# actuator_control_board_1_0_0.net
KiCad netlist of a schematic drawn in EAGLE
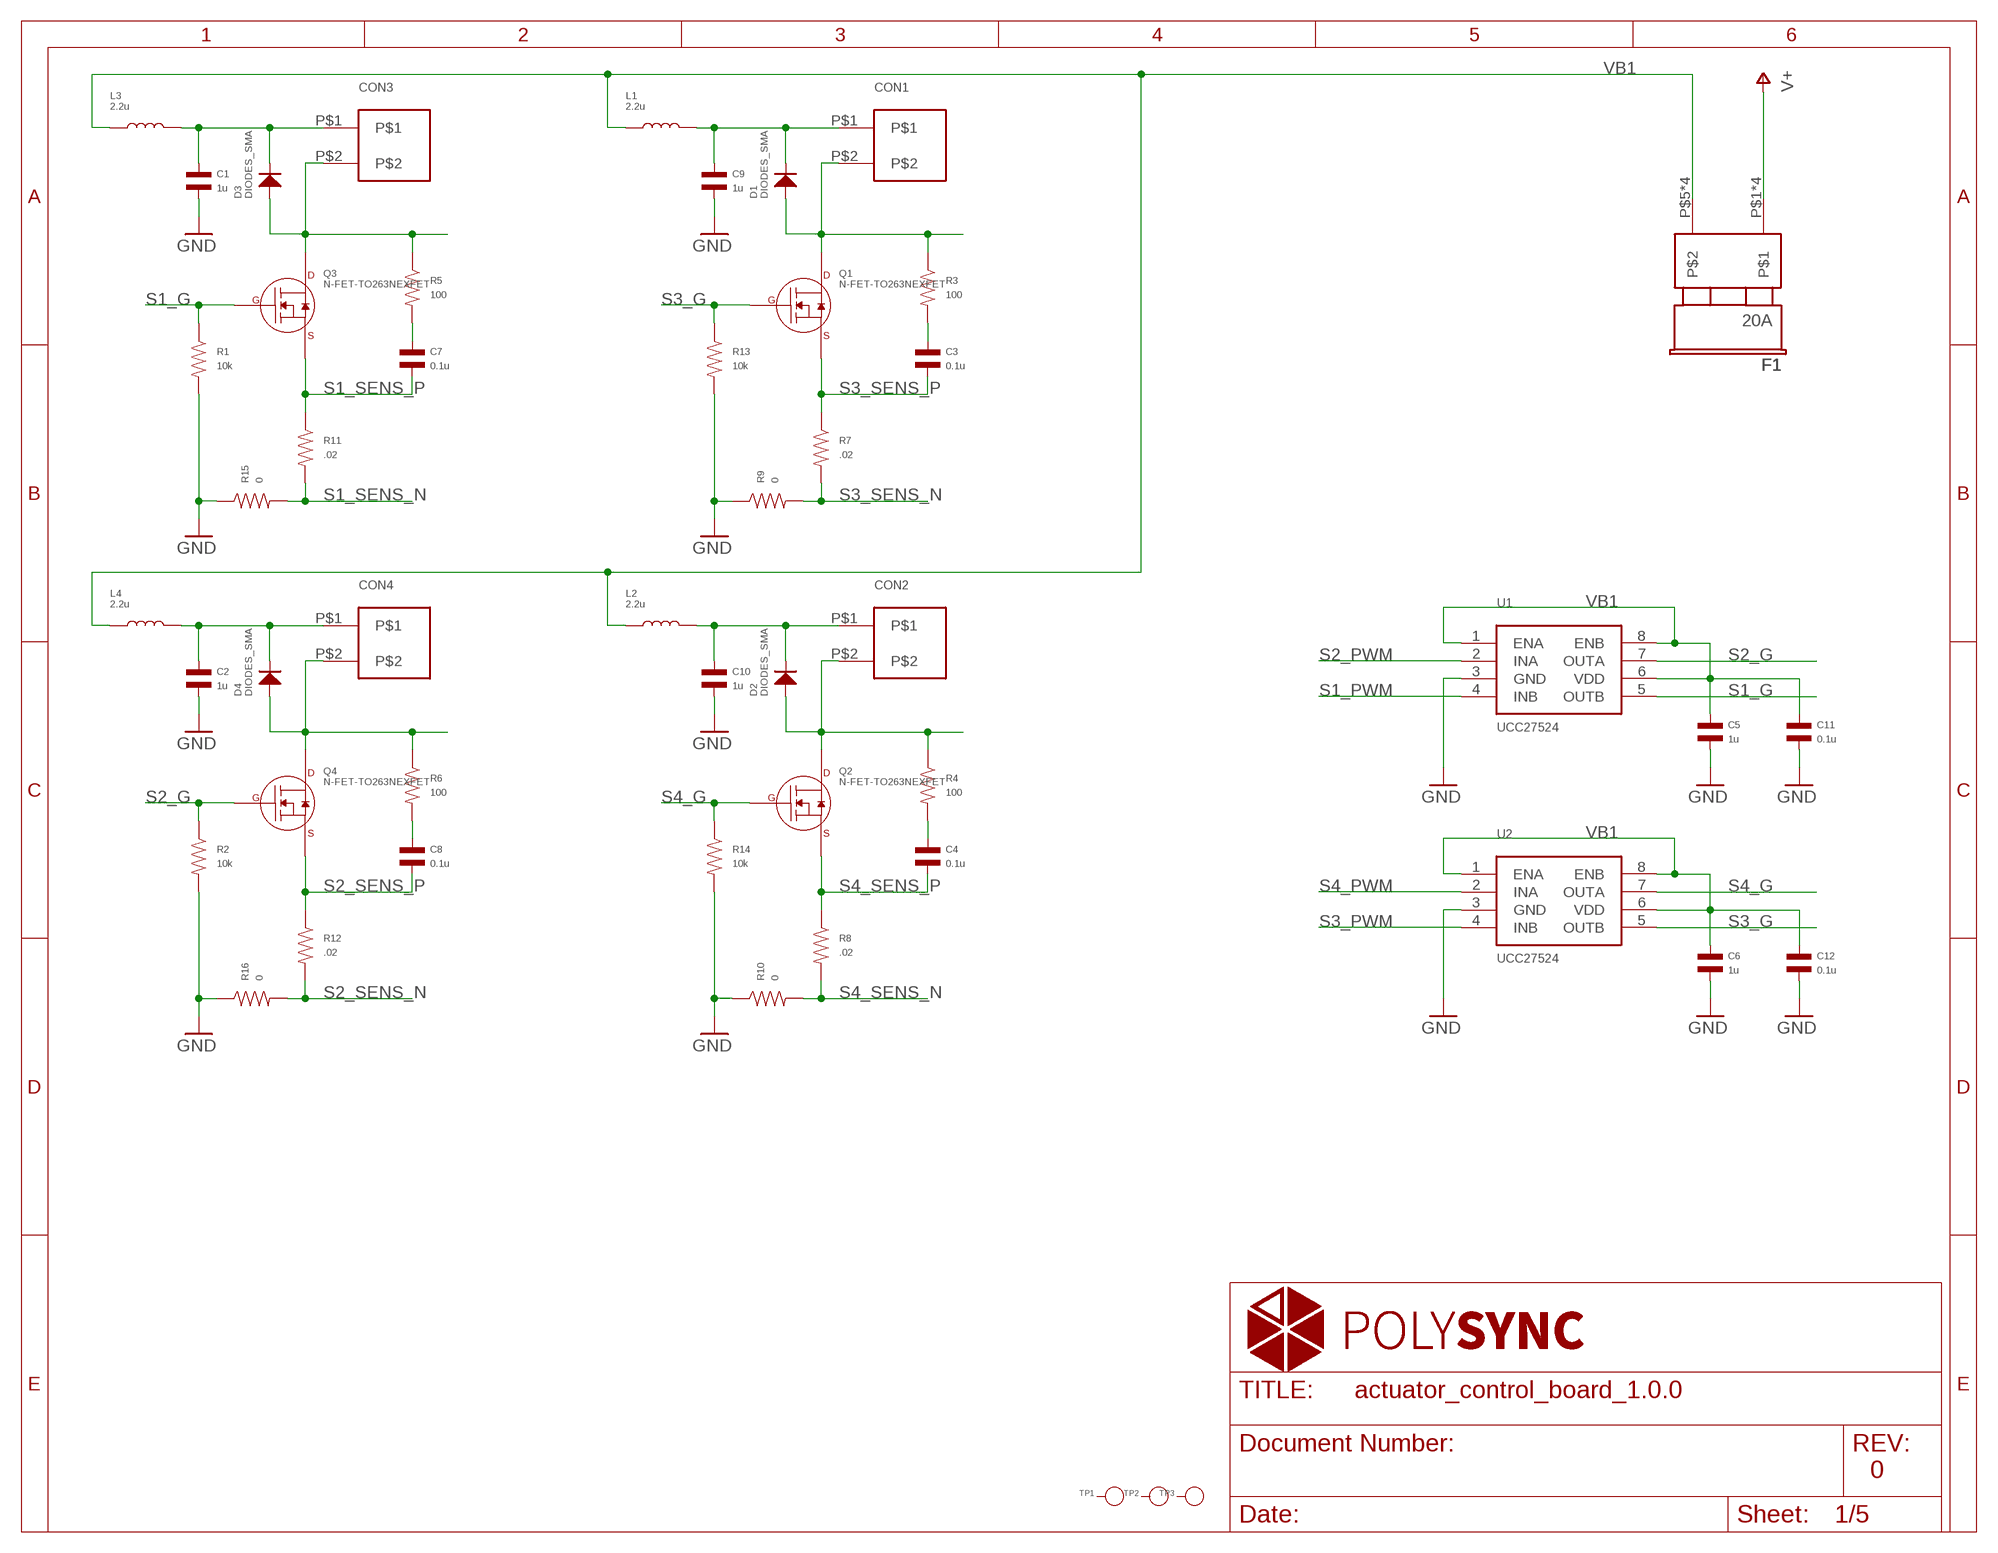
[diagram p0: schematic, sheet 1]
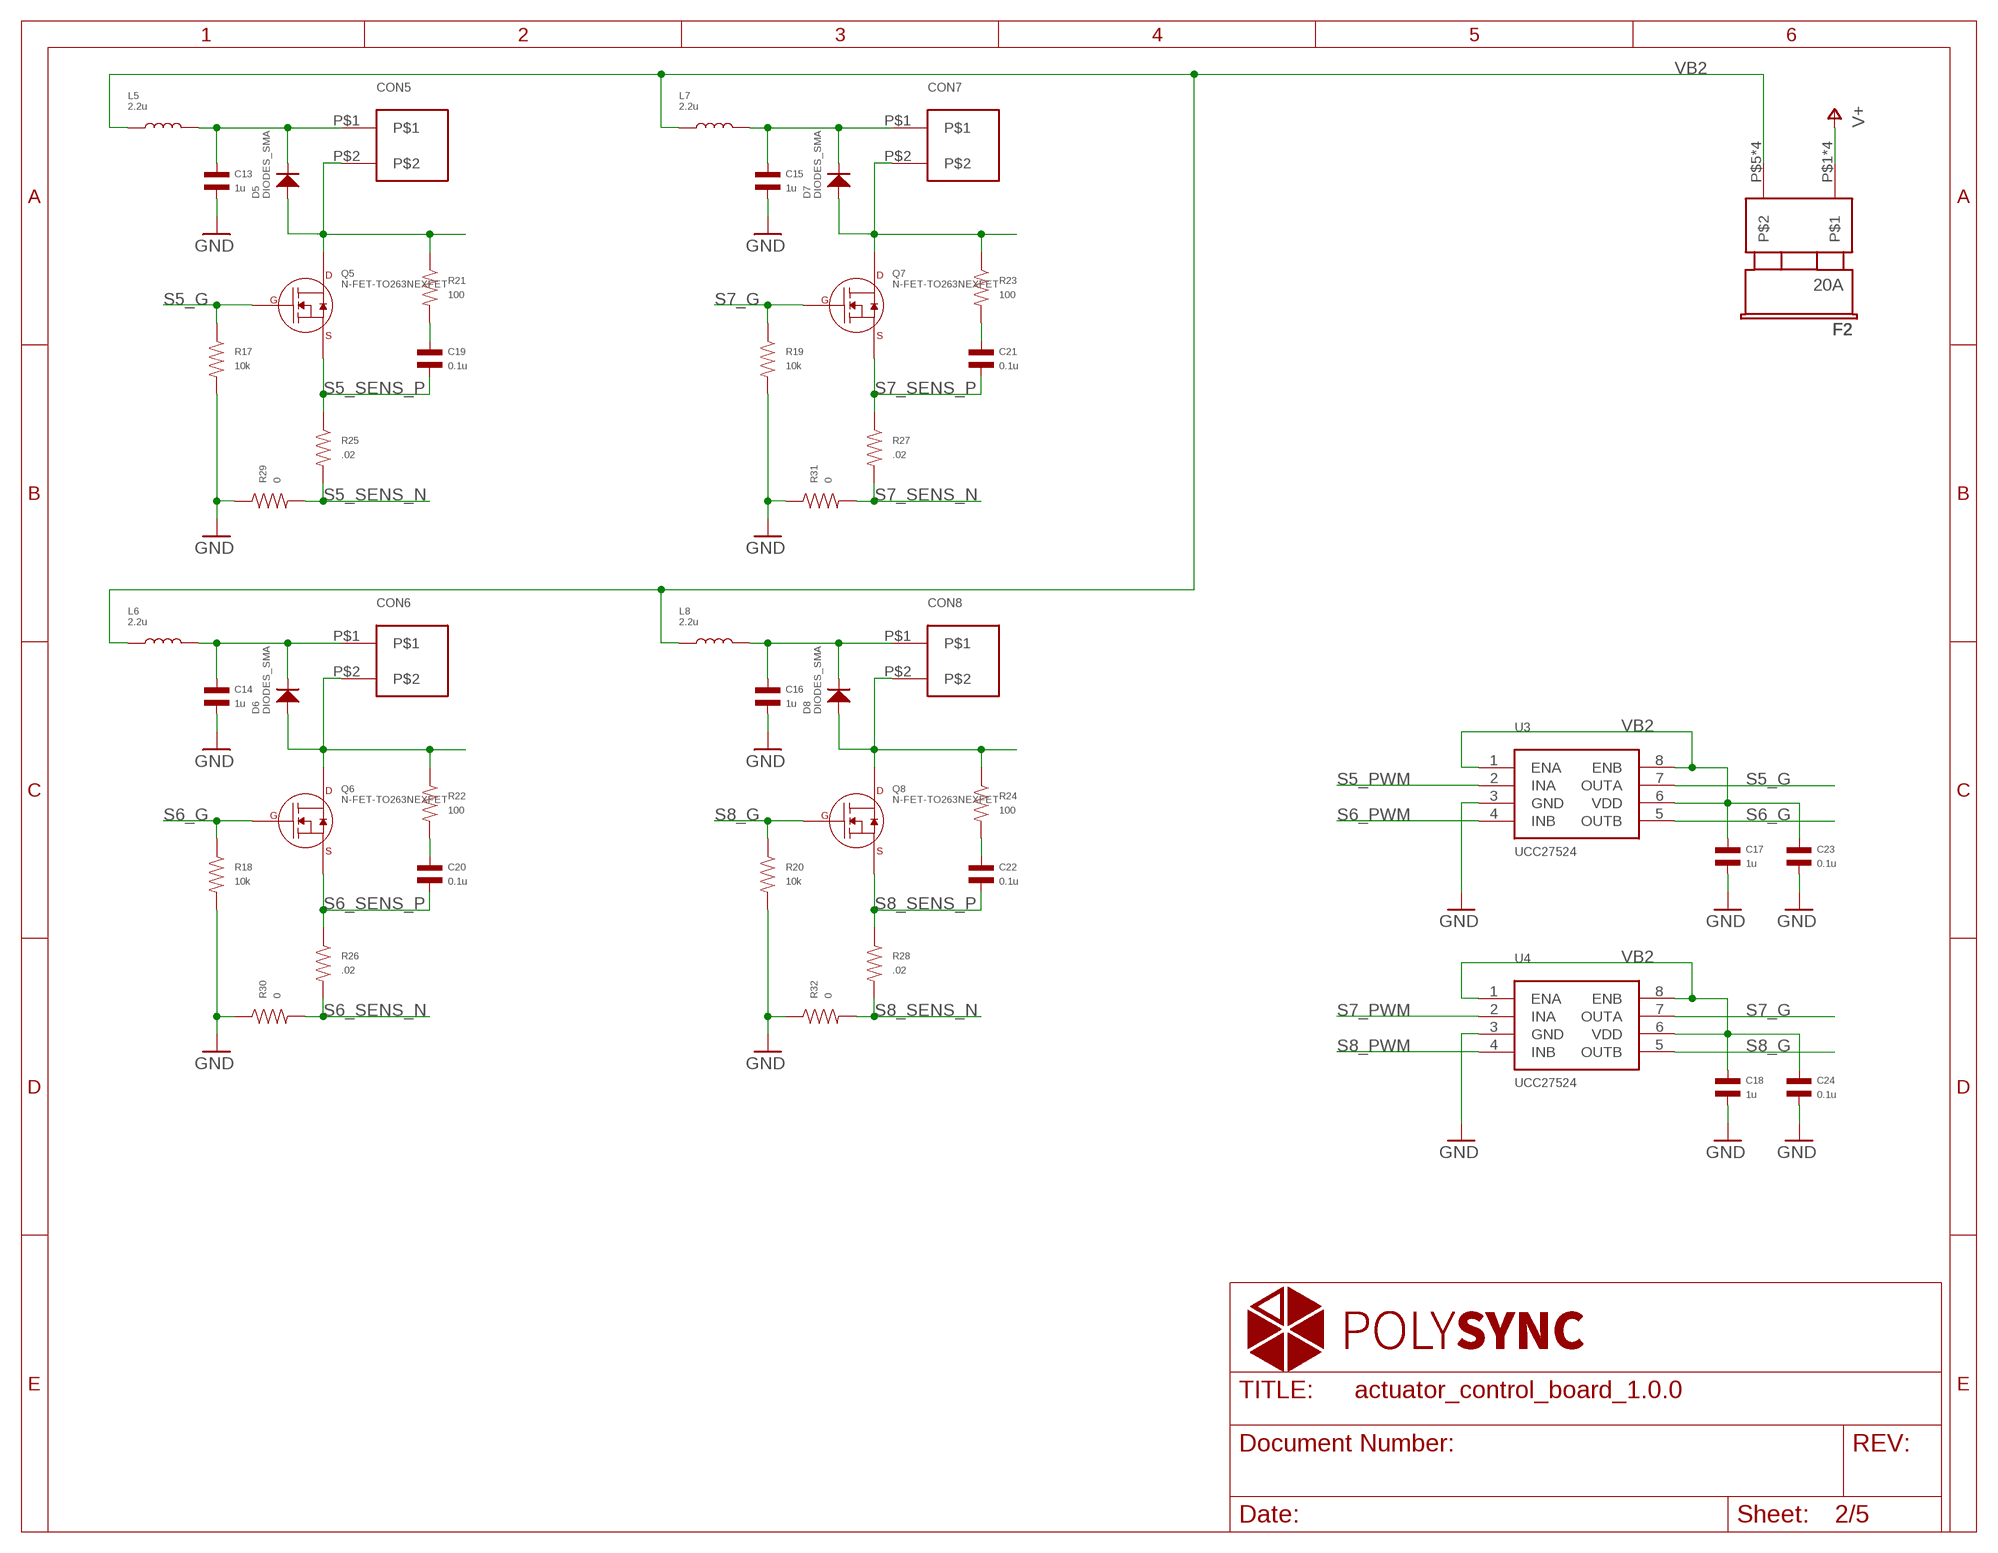
[diagram p1: schematic, sheet 2]
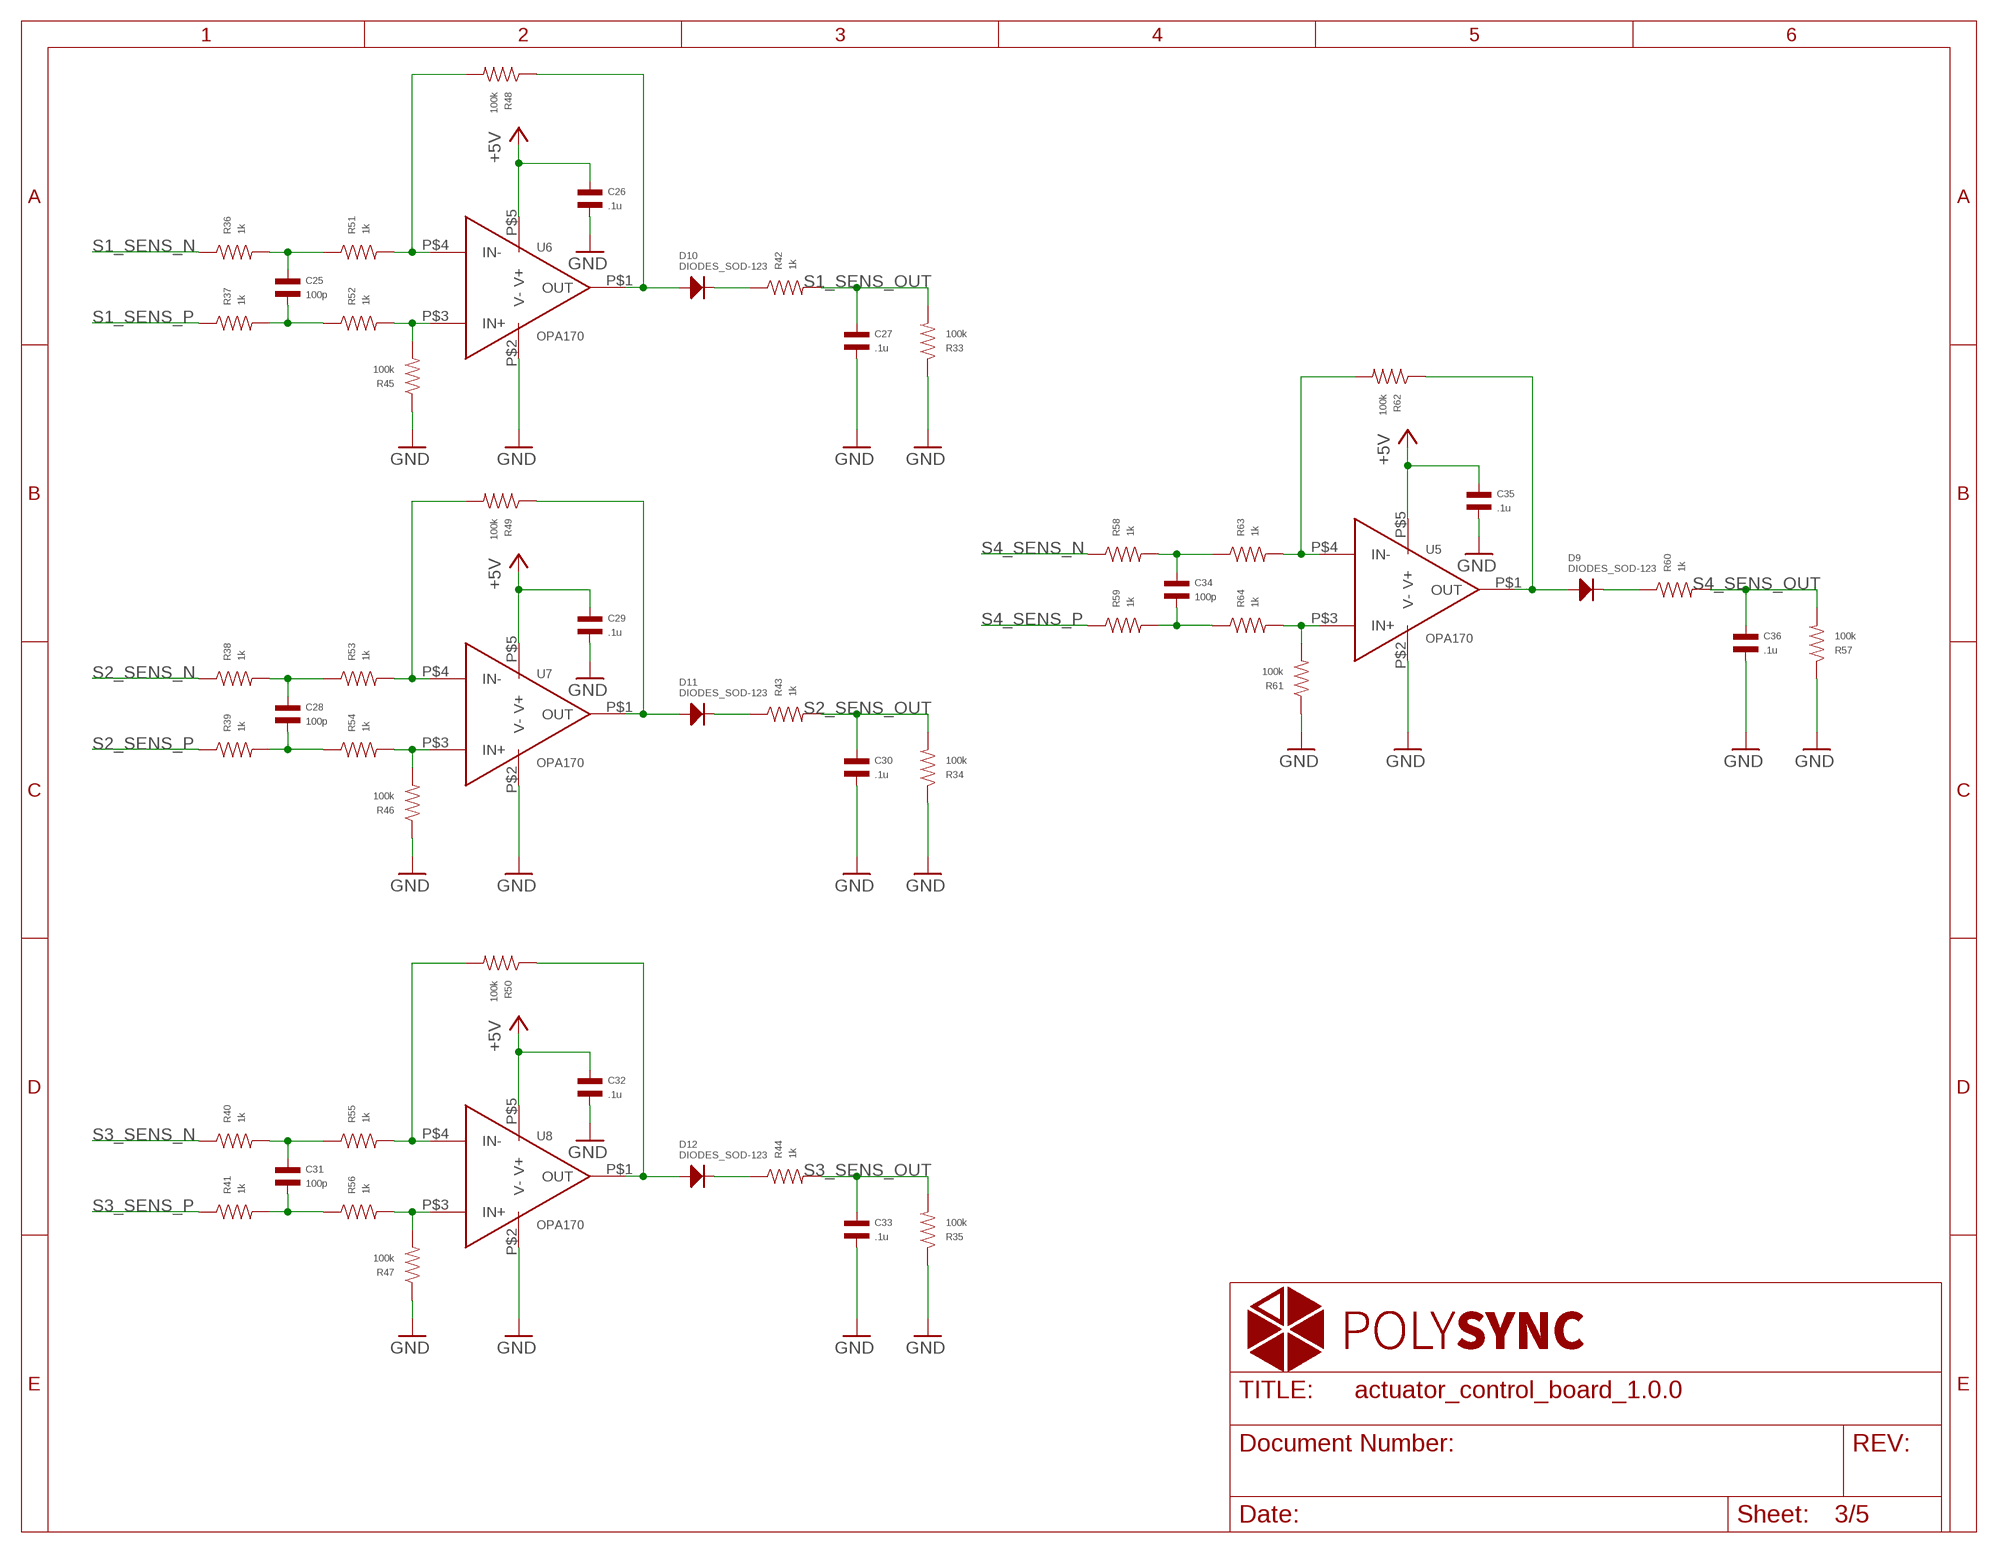
[diagram p2: schematic, sheet 3]
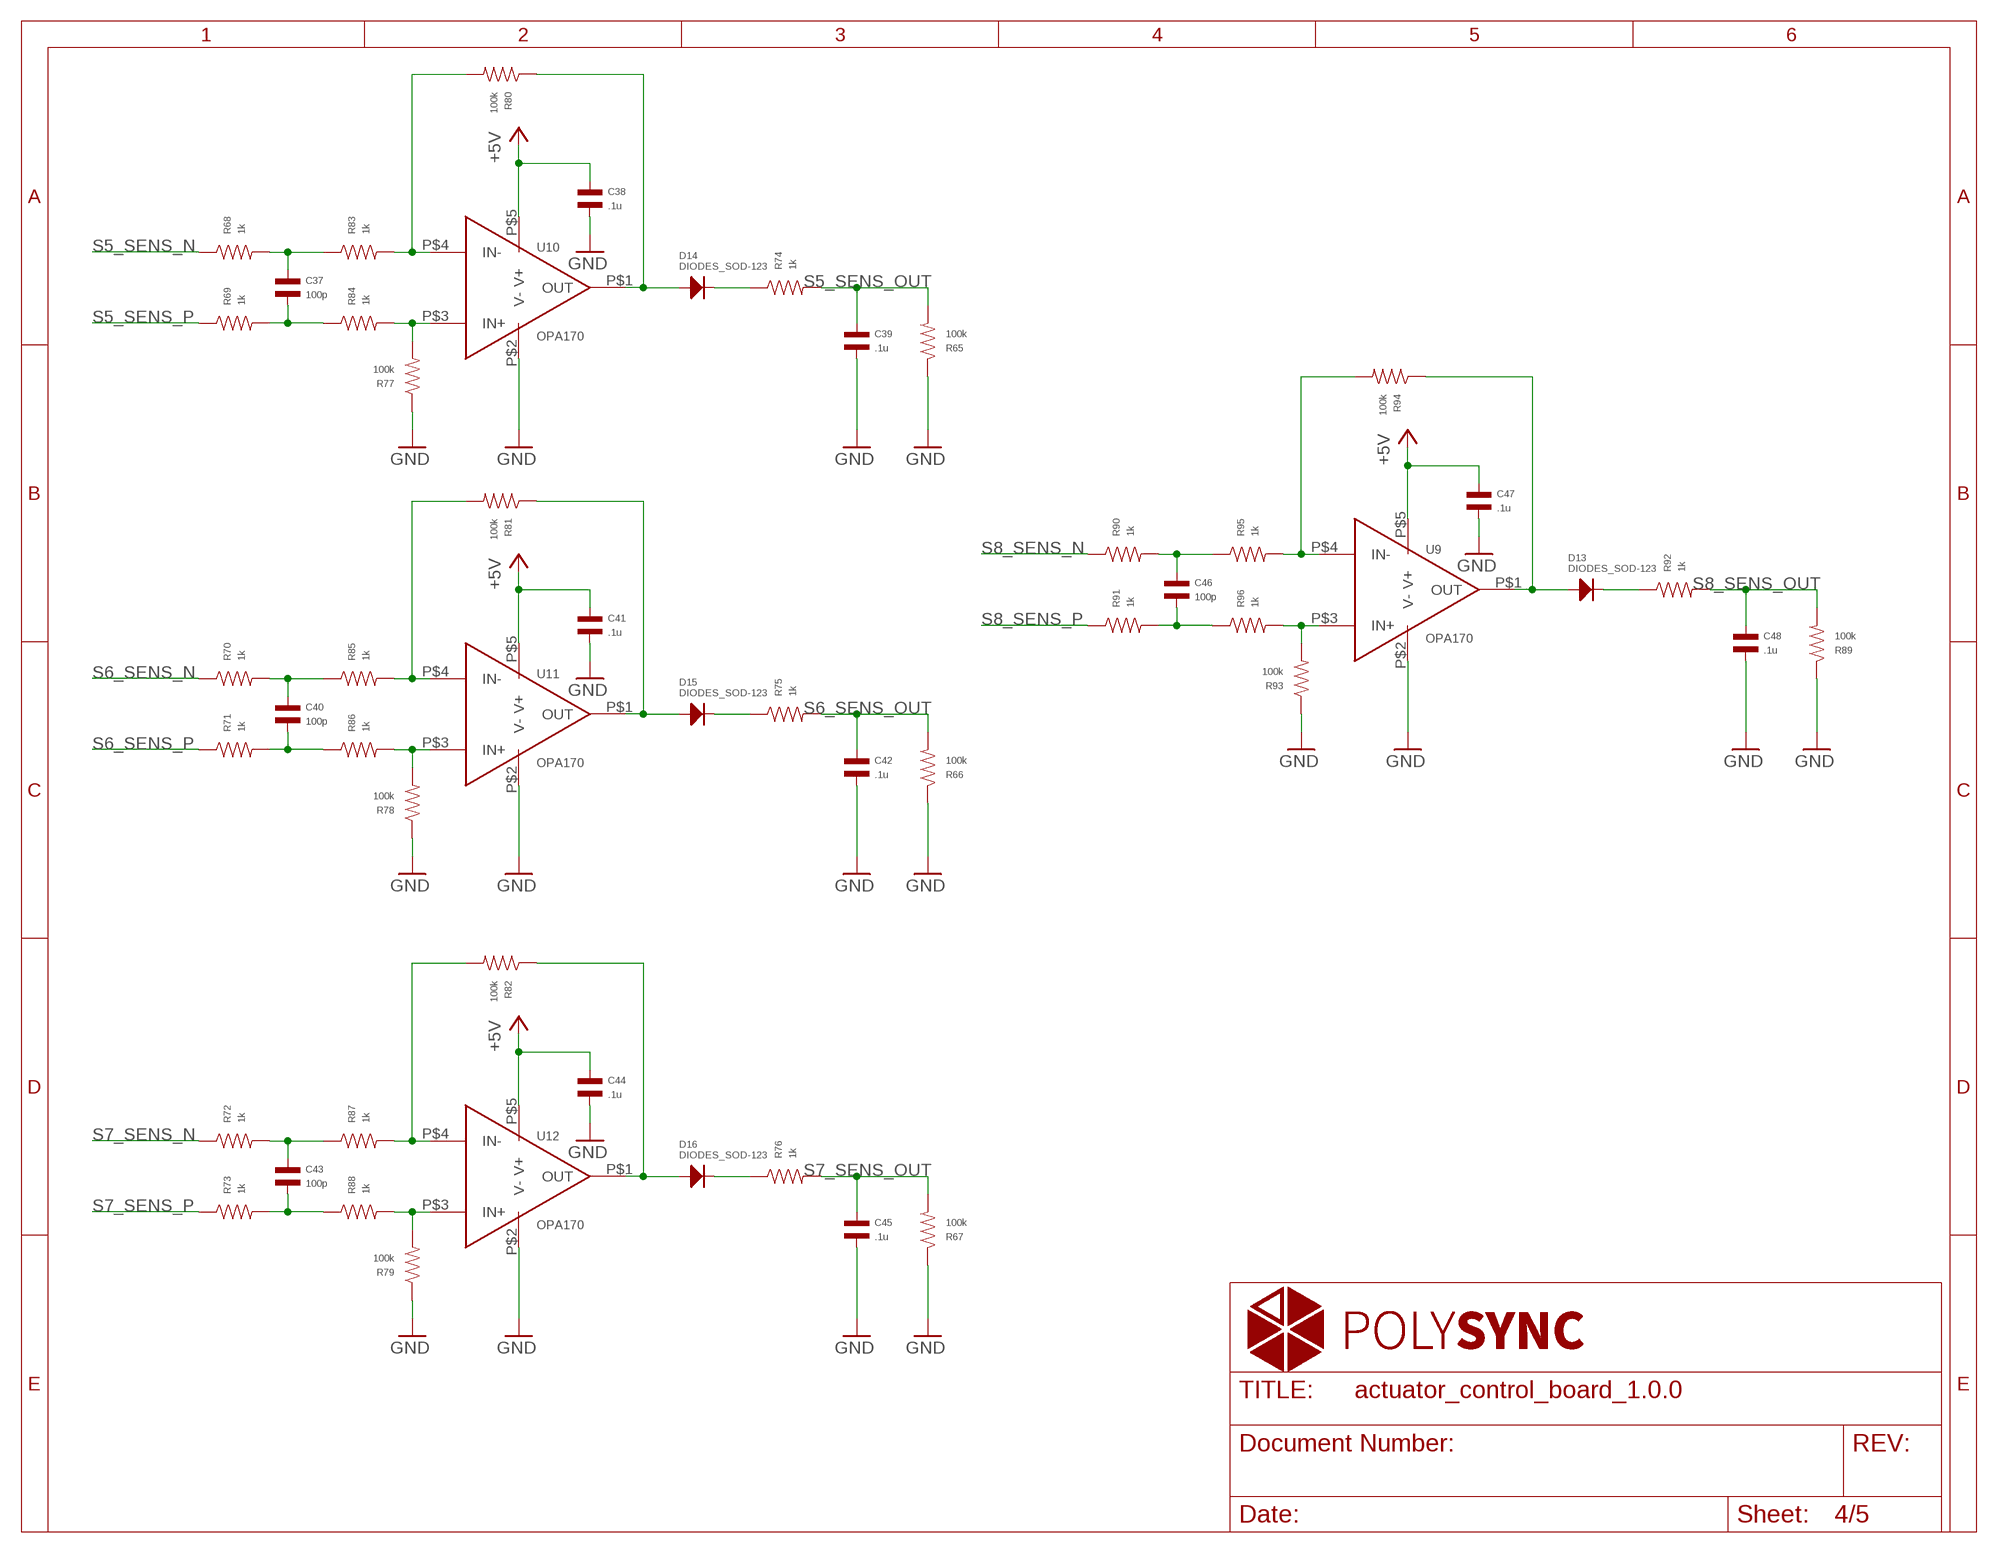
[diagram p3: schematic, sheet 4]
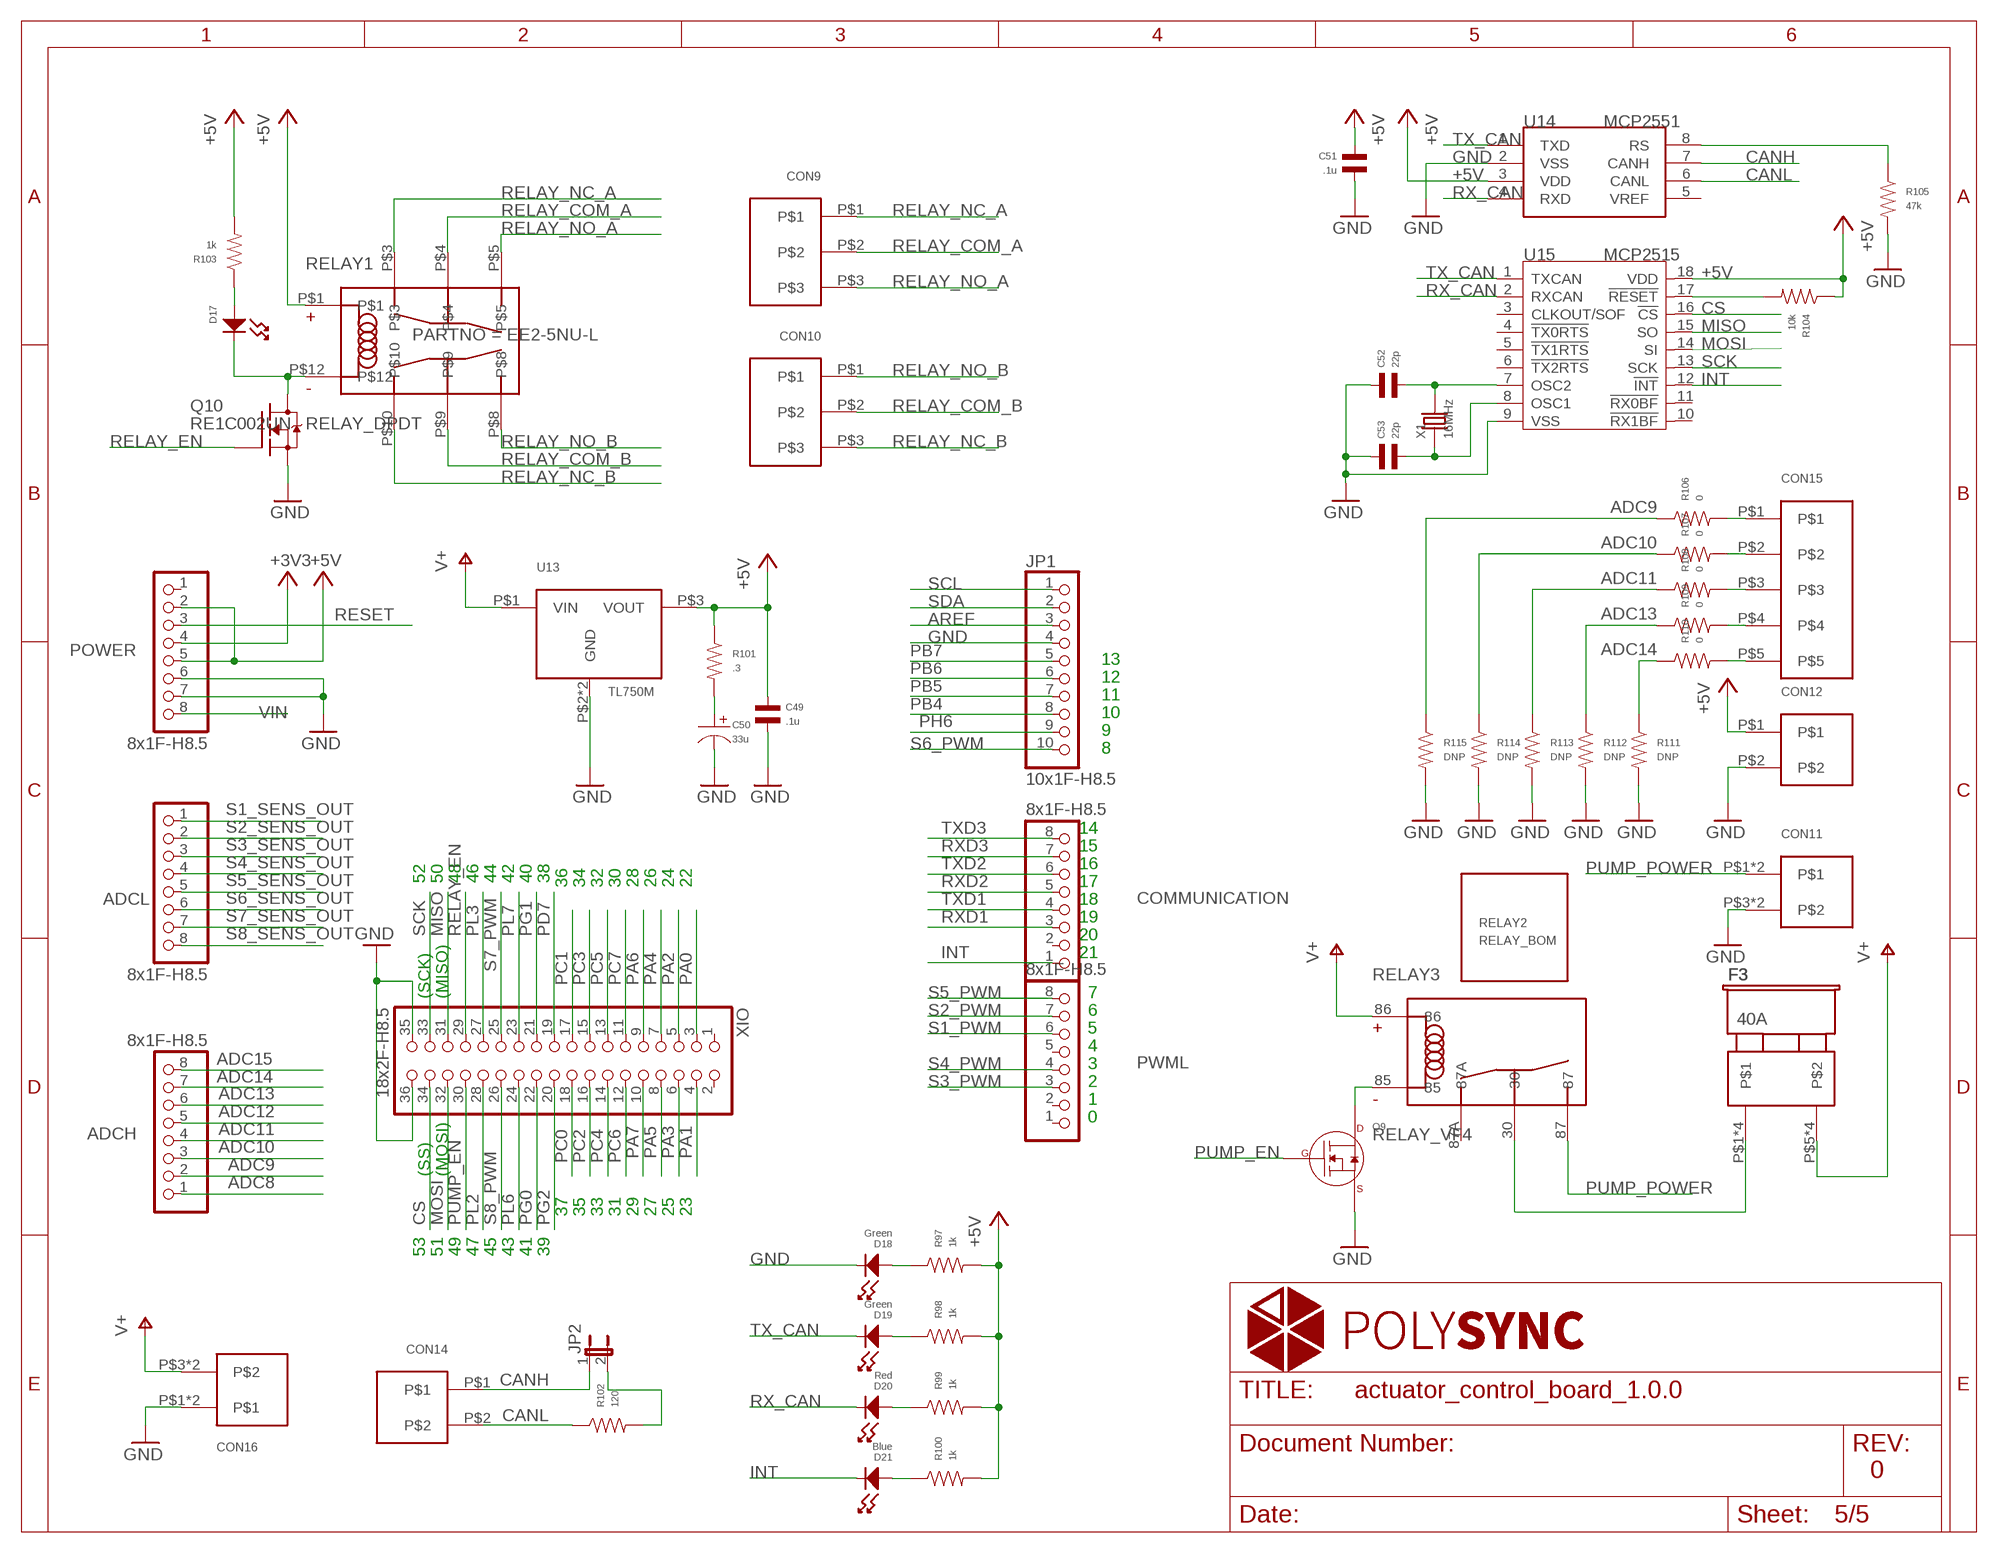
[diagram p4: schematic, sheet 5]

(export (version "E")
  (design (tool "Eeschema 10.0.6"))
  (components
    (comp (ref "C37")
      (value "100p")
      (footprint "eagle-import:C0402")
      (libsource (lib "eagle-import") (part "CAPACITOR_NP_0402"))
    )
    (comp (ref "C38")
      (value ".1u")
      (footprint "eagle-import:C0402")
      (libsource (lib "eagle-import") (part "CAPACITOR_NP_0402"))
    )
    (comp (ref "C39")
      (value ".1u")
      (footprint "eagle-import:C0402")
      (libsource (lib "eagle-import") (part "CAPACITOR_NP_0402"))
    )
    (comp (ref "C40")
      (value "100p")
      (footprint "eagle-import:C0402")
      (libsource (lib "eagle-import") (part "CAPACITOR_NP_0402"))
    )
    (comp (ref "C41")
      (value ".1u")
      (footprint "eagle-import:C0402")
      (libsource (lib "eagle-import") (part "CAPACITOR_NP_0402"))
    )
    (comp (ref "C42")
      (value ".1u")
      (footprint "eagle-import:C0402")
      (libsource (lib "eagle-import") (part "CAPACITOR_NP_0402"))
    )
    (comp (ref "C43")
      (value "100p")
      (footprint "eagle-import:C0402")
      (libsource (lib "eagle-import") (part "CAPACITOR_NP_0402"))
    )
    (comp (ref "C44")
      (value ".1u")
      (footprint "eagle-import:C0402")
      (libsource (lib "eagle-import") (part "CAPACITOR_NP_0402"))
    )
    (comp (ref "C45")
      (value ".1u")
      (footprint "eagle-import:C0402")
      (libsource (lib "eagle-import") (part "CAPACITOR_NP_0402"))
    )
    (comp (ref "C46")
      (value "100p")
      (footprint "eagle-import:C0402")
      (libsource (lib "eagle-import") (part "CAPACITOR_NP_0402"))
    )
    (comp (ref "C47")
      (value ".1u")
      (footprint "eagle-import:C0402")
      (libsource (lib "eagle-import") (part "CAPACITOR_NP_0402"))
    )
    (comp (ref "C48")
      (value ".1u")
      (footprint "eagle-import:C0402")
      (libsource (lib "eagle-import") (part "CAPACITOR_NP_0402"))
    )
    (comp (ref "D13")
      (value "DIODES_SOD-123")
      (footprint "eagle-import:SOD-123")
      (fields (field (name "HOUSEPART") "NO"))
      (libsource (lib "eagle-import") (part "DIODES_SOD-123"))
    )
    (comp (ref "D14")
      (value "DIODES_SOD-123")
      (footprint "eagle-import:SOD-123")
      (fields (field (name "HOUSEPART") "NO"))
      (libsource (lib "eagle-import") (part "DIODES_SOD-123"))
    )
    (comp (ref "D15")
      (value "DIODES_SOD-123")
      (footprint "eagle-import:SOD-123")
      (fields (field (name "HOUSEPART") "NO"))
      (libsource (lib "eagle-import") (part "DIODES_SOD-123"))
    )
    (comp (ref "D16")
      (value "DIODES_SOD-123")
      (footprint "eagle-import:SOD-123")
      (fields (field (name "HOUSEPART") "NO"))
      (libsource (lib "eagle-import") (part "DIODES_SOD-123"))
    )
    (comp (ref "R65")
      (value "100k")
      (footprint "eagle-import:R0402")
      (libsource (lib "eagle-import") (part "RESISTOR_0402"))
    )
    (comp (ref "R66")
      (value "100k")
      (footprint "eagle-import:R0402")
      (libsource (lib "eagle-import") (part "RESISTOR_0402"))
    )
    (comp (ref "R67")
      (value "100k")
      (footprint "eagle-import:R0402")
      (libsource (lib "eagle-import") (part "RESISTOR_0402"))
    )
    (comp (ref "R68")
      (value "1k")
      (footprint "eagle-import:R0402")
      (libsource (lib "eagle-import") (part "RESISTOR_0402"))
    )
    (comp (ref "R69")
      (value "1k")
      (footprint "eagle-import:R0402")
      (libsource (lib "eagle-import") (part "RESISTOR_0402"))
    )
    (comp (ref "R70")
      (value "1k")
      (footprint "eagle-import:R0402")
      (libsource (lib "eagle-import") (part "RESISTOR_0402"))
    )
    (comp (ref "R71")
      (value "1k")
      (footprint "eagle-import:R0402")
      (libsource (lib "eagle-import") (part "RESISTOR_0402"))
    )
    (comp (ref "R72")
      (value "1k")
      (footprint "eagle-import:R0402")
      (libsource (lib "eagle-import") (part "RESISTOR_0402"))
    )
    (comp (ref "R73")
      (value "1k")
      (footprint "eagle-import:R0402")
      (libsource (lib "eagle-import") (part "RESISTOR_0402"))
    )
    (comp (ref "R74")
      (value "1k")
      (footprint "eagle-import:R0402")
      (libsource (lib "eagle-import") (part "RESISTOR_0402"))
    )
    (comp (ref "R75")
      (value "1k")
      (footprint "eagle-import:R0402")
      (libsource (lib "eagle-import") (part "RESISTOR_0402"))
    )
    (comp (ref "R76")
      (value "1k")
      (footprint "eagle-import:R0402")
      (libsource (lib "eagle-import") (part "RESISTOR_0402"))
    )
    (comp (ref "R77")
      (value "100k")
      (footprint "eagle-import:R0402")
      (libsource (lib "eagle-import") (part "RESISTOR_0402"))
    )
    (comp (ref "R78")
      (value "100k")
      (footprint "eagle-import:R0402")
      (libsource (lib "eagle-import") (part "RESISTOR_0402"))
    )
    (comp (ref "R79")
      (value "100k")
      (footprint "eagle-import:R0402")
      (libsource (lib "eagle-import") (part "RESISTOR_0402"))
    )
    (comp (ref "R80")
      (value "100k")
      (footprint "eagle-import:R0402")
      (libsource (lib "eagle-import") (part "RESISTOR_0402"))
    )
    (comp (ref "R81")
      (value "100k")
      (footprint "eagle-import:R0402")
      (libsource (lib "eagle-import") (part "RESISTOR_0402"))
    )
    (comp (ref "R82")
      (value "100k")
      (footprint "eagle-import:R0402")
      (libsource (lib "eagle-import") (part "RESISTOR_0402"))
    )
    (comp (ref "R83")
      (value "1k")
      (footprint "eagle-import:R0402")
      (libsource (lib "eagle-import") (part "RESISTOR_0402"))
    )
    (comp (ref "R84")
      (value "1k")
      (footprint "eagle-import:R0402")
      (libsource (lib "eagle-import") (part "RESISTOR_0402"))
    )
    (comp (ref "R85")
      (value "1k")
      (footprint "eagle-import:R0402")
      (libsource (lib "eagle-import") (part "RESISTOR_0402"))
    )
    (comp (ref "R86")
      (value "1k")
      (footprint "eagle-import:R0402")
      (libsource (lib "eagle-import") (part "RESISTOR_0402"))
    )
    (comp (ref "R87")
      (value "1k")
      (footprint "eagle-import:R0402")
      (libsource (lib "eagle-import") (part "RESISTOR_0402"))
    )
    (comp (ref "R88")
      (value "1k")
      (footprint "eagle-import:R0402")
      (libsource (lib "eagle-import") (part "RESISTOR_0402"))
    )
    (comp (ref "R89")
      (value "100k")
      (footprint "eagle-import:R0402")
      (libsource (lib "eagle-import") (part "RESISTOR_0402"))
    )
    (comp (ref "R90")
      (value "1k")
      (footprint "eagle-import:R0402")
      (libsource (lib "eagle-import") (part "RESISTOR_0402"))
    )
    (comp (ref "R91")
      (value "1k")
      (footprint "eagle-import:R0402")
      (libsource (lib "eagle-import") (part "RESISTOR_0402"))
    )
    (comp (ref "R92")
      (value "1k")
      (footprint "eagle-import:R0402")
      (libsource (lib "eagle-import") (part "RESISTOR_0402"))
    )
    (comp (ref "R93")
      (value "100k")
      (footprint "eagle-import:R0402")
      (libsource (lib "eagle-import") (part "RESISTOR_0402"))
    )
    (comp (ref "R94")
      (value "100k")
      (footprint "eagle-import:R0402")
      (libsource (lib "eagle-import") (part "RESISTOR_0402"))
    )
    (comp (ref "R95")
      (value "1k")
      (footprint "eagle-import:R0402")
      (libsource (lib "eagle-import") (part "RESISTOR_0402"))
    )
    (comp (ref "R96")
      (value "1k")
      (footprint "eagle-import:R0402")
      (libsource (lib "eagle-import") (part "RESISTOR_0402"))
    )
    (comp (ref "U9")
      (value "OPA170")
      (footprint "eagle-import:SOT-23-5")
      (libsource (lib "eagle-import") (part "OPA170"))
    )
    (comp (ref "U10")
      (value "OPA170")
      (footprint "eagle-import:SOT-23-5")
      (libsource (lib "eagle-import") (part "OPA170"))
    )
    (comp (ref "U11")
      (value "OPA170")
      (footprint "eagle-import:SOT-23-5")
      (libsource (lib "eagle-import") (part "OPA170"))
    )
    (comp (ref "U12")
      (value "OPA170")
      (footprint "eagle-import:SOT-23-5")
      (libsource (lib "eagle-import") (part "OPA170"))
    )
    (comp (ref "C1")
      (value "1u")
      (footprint "eagle-import:C1206")
      (libsource (lib "eagle-import") (part "CAPACITOR_NP_1206"))
    )
    (comp (ref "C2")
      (value "1u")
      (footprint "eagle-import:C1206")
      (libsource (lib "eagle-import") (part "CAPACITOR_NP_1206"))
    )
    (comp (ref "C3")
      (value "0.1u")
      (footprint "eagle-import:C0805")
      (libsource (lib "eagle-import") (part "CAPACITOR_NP_0805"))
    )
    (comp (ref "C4")
      (value "0.1u")
      (footprint "eagle-import:C0805")
      (libsource (lib "eagle-import") (part "CAPACITOR_NP_0805"))
    )
    (comp (ref "C5")
      (value "1u")
      (footprint "eagle-import:C1206")
      (libsource (lib "eagle-import") (part "CAPACITOR_NP_1206"))
    )
    (comp (ref "C6")
      (value "1u")
      (footprint "eagle-import:C1206")
      (libsource (lib "eagle-import") (part "CAPACITOR_NP_1206"))
    )
    (comp (ref "C7")
      (value "0.1u")
      (footprint "eagle-import:C0805")
      (libsource (lib "eagle-import") (part "CAPACITOR_NP_0805"))
    )
    (comp (ref "C8")
      (value "0.1u")
      (footprint "eagle-import:C0805")
      (libsource (lib "eagle-import") (part "CAPACITOR_NP_0805"))
    )
    (comp (ref "C9")
      (value "1u")
      (footprint "eagle-import:C1206")
      (libsource (lib "eagle-import") (part "CAPACITOR_NP_1206"))
    )
    (comp (ref "C10")
      (value "1u")
      (footprint "eagle-import:C1206")
      (libsource (lib "eagle-import") (part "CAPACITOR_NP_1206"))
    )
    (comp (ref "C11")
      (value "0.1u")
      (footprint "eagle-import:C0805")
      (libsource (lib "eagle-import") (part "CAPACITOR_NP_0805"))
    )
    (comp (ref "C12")
      (value "0.1u")
      (footprint "eagle-import:C0805")
      (libsource (lib "eagle-import") (part "CAPACITOR_NP_0805"))
    )
    (comp (ref "CON1")
      (value "CON23.5MM")
      (footprint "eagle-import:PHOENIX_2_45")
      (libsource (lib "eagle-import") (part "CON23.5MM"))
    )
    (comp (ref "CON2")
      (value "CON23.5MM")
      (footprint "eagle-import:PHOENIX_2_45")
      (libsource (lib "eagle-import") (part "CON23.5MM"))
    )
    (comp (ref "CON3")
      (value "CON23.5MM")
      (footprint "eagle-import:PHOENIX_2_45")
      (libsource (lib "eagle-import") (part "CON23.5MM"))
    )
    (comp (ref "CON4")
      (value "CON23.5MM")
      (footprint "eagle-import:PHOENIX_2_45")
      (libsource (lib "eagle-import") (part "CON23.5MM"))
    )
    (comp (ref "D1")
      (value "DIODES_SMA")
      (footprint "eagle-import:SMA")
      (fields (field (name "HOUSEPART") "NO"))
      (libsource (lib "eagle-import") (part "DIODES_SMA"))
    )
    (comp (ref "D2")
      (value "DIODES_SMA")
      (footprint "eagle-import:SMA")
      (fields (field (name "HOUSEPART") "NO"))
      (libsource (lib "eagle-import") (part "DIODES_SMA"))
    )
    (comp (ref "D3")
      (value "DIODES_SMA")
      (footprint "eagle-import:SMA")
      (fields
        (field (name "HOUSEPART") "NO")
        (field (name "MFG") "Diodes Inc")
        (field (name "MPN") "US1B-13-F")
      )
      (libsource (lib "eagle-import") (part "DIODES_SMA"))
    )
    (comp (ref "D4")
      (value "DIODES_SMA")
      (footprint "eagle-import:SMA")
      (fields (field (name "HOUSEPART") "NO"))
      (libsource (lib "eagle-import") (part "DIODES_SMA"))
    )
    (comp (ref "F1")
      (value "20A")
      (footprint "eagle-import:FUSE_ATO")
      (fields (field (name "MFG") "Littelfuse") (field (name "PARTNO") "178.6165.0001"))
      (libsource (lib "eagle-import") (part "FUSE"))
    )
    (comp (ref "L1")
      (value "2.2u")
      (footprint "eagle-import:SRP7050")
      (fields (field (name "MFG") "Bourns") (field (name "PARTNO") "SRP7050TA-2R2M"))
      (libsource (lib "eagle-import") (part "INDUCTORSRP7050"))
    )
    (comp (ref "L2")
      (value "2.2u")
      (footprint "eagle-import:SRP7050")
      (fields (field (name "MFG") "Bourns") (field (name "PARTNO") "SRP7050TA-2R2M"))
      (libsource (lib "eagle-import") (part "INDUCTORSRP7050"))
    )
    (comp (ref "L3")
      (value "2.2u")
      (footprint "eagle-import:SRP7050")
      (fields (field (name "MFG") "Bourns") (field (name "PARTNO") "SRP7050TA-2R2M"))
      (libsource (lib "eagle-import") (part "INDUCTORSRP7050"))
    )
    (comp (ref "L4")
      (value "2.2u")
      (footprint "eagle-import:SRP7050")
      (fields (field (name "MFG") "Bourns") (field (name "PARTNO") "SRP7050TA-2R2M"))
      (libsource (lib "eagle-import") (part "INDUCTORSRP7050"))
    )
    (comp (ref "Q1")
      (value "N-FET-TO263NEXFET")
      (footprint "eagle-import:SON8-DQJ")
      (libsource (lib "eagle-import") (part "N-FET-TO263NEXFET"))
    )
    (comp (ref "Q2")
      (value "N-FET-TO263NEXFET")
      (footprint "eagle-import:SON8-DQJ")
      (libsource (lib "eagle-import") (part "N-FET-TO263NEXFET"))
    )
    (comp (ref "Q3")
      (value "N-FET-TO263NEXFET")
      (footprint "eagle-import:SON8-DQJ")
      (libsource (lib "eagle-import") (part "N-FET-TO263NEXFET"))
    )
    (comp (ref "Q4")
      (value "N-FET-TO263NEXFET")
      (footprint "eagle-import:SON8-DQJ")
      (libsource (lib "eagle-import") (part "N-FET-TO263NEXFET"))
    )
    (comp (ref "R1")
      (value "10k")
      (footprint "eagle-import:R0402")
      (libsource (lib "eagle-import") (part "RESISTOR_0402"))
    )
    (comp (ref "R2")
      (value "10k")
      (footprint "eagle-import:R0402")
      (libsource (lib "eagle-import") (part "RESISTOR_0402"))
    )
    (comp (ref "R3")
      (value "100")
      (footprint "eagle-import:R0805")
      (libsource (lib "eagle-import") (part "RESISTOR_0805"))
    )
    (comp (ref "R4")
      (value "100")
      (footprint "eagle-import:R0805")
      (libsource (lib "eagle-import") (part "RESISTOR_0805"))
    )
    (comp (ref "R5")
      (value "100")
      (footprint "eagle-import:R0805")
      (libsource (lib "eagle-import") (part "RESISTOR_0805"))
    )
    (comp (ref "R6")
      (value "100")
      (footprint "eagle-import:R0805")
      (libsource (lib "eagle-import") (part "RESISTOR_0805"))
    )
    (comp (ref "R7")
      (value ".02")
      (footprint "eagle-import:R1206")
      (libsource (lib "eagle-import") (part "RESISTOR_1206"))
    )
    (comp (ref "R8")
      (value ".02")
      (footprint "eagle-import:R1206")
      (libsource (lib "eagle-import") (part "RESISTOR_1206"))
    )
    (comp (ref "R9")
      (value "0")
      (footprint "eagle-import:R0805")
      (libsource (lib "eagle-import") (part "RESISTOR_0805"))
    )
    (comp (ref "R10")
      (value "0")
      (footprint "eagle-import:R0805")
      (libsource (lib "eagle-import") (part "RESISTOR_0805"))
    )
    (comp (ref "R11")
      (value ".02")
      (footprint "eagle-import:R1206")
      (libsource (lib "eagle-import") (part "RESISTOR_1206"))
    )
    (comp (ref "R12")
      (value ".02")
      (footprint "eagle-import:R1206")
      (libsource (lib "eagle-import") (part "RESISTOR_1206"))
    )
    (comp (ref "R13")
      (value "10k")
      (footprint "eagle-import:R0402")
      (libsource (lib "eagle-import") (part "RESISTOR_0402"))
    )
    (comp (ref "R14")
      (value "10k")
      (footprint "eagle-import:R0402")
      (libsource (lib "eagle-import") (part "RESISTOR_0402"))
    )
    (comp (ref "R15")
      (value "0")
      (footprint "eagle-import:R0805")
      (libsource (lib "eagle-import") (part "RESISTOR_0805"))
    )
    (comp (ref "R16")
      (value "0")
      (footprint "eagle-import:R0805")
      (libsource (lib "eagle-import") (part "RESISTOR_0805"))
    )
    (comp (ref "TP1")
      (value "PAD-TEST-POINT'4545'")
      (footprint "eagle-import:TP_4545")
      (fields (field (name "PARTNO") "DNP"))
      (libsource (lib "eagle-import") (part "PAD-TEST-POINT'4545'"))
    )
    (comp (ref "TP2")
      (value "PAD-TEST-POINT'4545'")
      (footprint "eagle-import:TP_4545")
      (fields (field (name "PARTNO") "DNP"))
      (libsource (lib "eagle-import") (part "PAD-TEST-POINT'4545'"))
    )
    (comp (ref "TP3")
      (value "PAD-TEST-POINT'4545'")
      (footprint "eagle-import:TP_4545")
      (fields (field (name "PARTNO") "DNP"))
      (libsource (lib "eagle-import") (part "PAD-TEST-POINT'4545'"))
    )
    (comp (ref "U1")
      (value "UCC27524")
      (footprint "eagle-import:SOIC-8")
      (libsource (lib "eagle-import") (part "UCC27524"))
    )
    (comp (ref "U2")
      (value "UCC27524")
      (footprint "eagle-import:SOIC-8")
      (libsource (lib "eagle-import") (part "UCC27524"))
    )
    (comp (ref "ADCH")
      (value "8x1F-H8.5")
      (footprint "eagle-import:1X08")
      (libsource (lib "eagle-import") (part "PINHD-1X8"))
    )
    (comp (ref "ADCL")
      (value "8x1F-H8.5")
      (footprint "eagle-import:1X08")
      (libsource (lib "eagle-import") (part "PINHD-1X8"))
    )
    (comp (ref "C49")
      (value ".1u")
      (footprint "eagle-import:C0402")
      (libsource (lib "eagle-import") (part "CAPACITOR_NP_0402"))
    )
    (comp (ref "C50")
      (value "33u")
      (footprint "eagle-import:CP1206")
      (libsource (lib "eagle-import") (part "CAPACITOR_P"))
    )
    (comp (ref "C51")
      (value ".1u")
      (footprint "eagle-import:C0402")
      (libsource (lib "eagle-import") (part "CAPACITOR_NP_0402"))
    )
    (comp (ref "C52")
      (value "22p")
      (footprint "eagle-import:C0402")
      (libsource (lib "eagle-import") (part "CAPACITOR_NP_0402"))
    )
    (comp (ref "C53")
      (value "22p")
      (footprint "eagle-import:C0402")
      (libsource (lib "eagle-import") (part "CAPACITOR_NP_0402"))
    )
    (comp (ref "COMMUNICATION")
      (value "8x1F-H8.5")
      (footprint "eagle-import:1X08")
      (libsource (lib "eagle-import") (part "PINHD-1X8"))
    )
    (comp (ref "CON9")
      (value "CON3")
      (footprint "eagle-import:PHOENIX_3_45")
      (libsource (lib "eagle-import") (part "CON3"))
    )
    (comp (ref "CON10")
      (value "CON3")
      (footprint "eagle-import:PHOENIX_3_45")
      (libsource (lib "eagle-import") (part "CON3"))
    )
    (comp (ref "CON11")
      (value "CON210.16MM")
      (footprint "eagle-import:PHOENIX_2_10.16MM")
      (fields (field (name "MFG") "PHOENIXCONTACT") (field (name "PARTNO") "1773976"))
      (libsource (lib "eagle-import") (part "CON210.16MM"))
    )
    (comp (ref "CON12")
      (value "CON23.5MM")
      (footprint "eagle-import:PHOENIX_2_45")
      (libsource (lib "eagle-import") (part "CON23.5MM"))
    )
    (comp (ref "CON14")
      (value "CON23.5MM")
      (footprint "eagle-import:PHOENIX_2_45")
      (libsource (lib "eagle-import") (part "CON23.5MM"))
    )
    (comp (ref "CON15")
      (value "CON5")
      (footprint "eagle-import:PHOENIX_5_45")
      (libsource (lib "eagle-import") (part "CON5"))
    )
    (comp (ref "CON16")
      (value "CON210.16MM")
      (footprint "eagle-import:PHOENIX_2_10.16MM")
      (fields (field (name "MFG") "PHOENIXCONTACT") (field (name "PARTNO") "1773976"))
      (libsource (lib "eagle-import") (part "CON210.16MM"))
    )
    (comp (ref "D17")
      (value "LED_SINGLE-0603")
      (footprint "eagle-import:LED0603")
      (fields (field (name "HOUSEPART") "NO"))
      (libsource (lib "eagle-import") (part "LED_SINGLE-0603"))
    )
    (comp (ref "D18")
      (value "Green")
      (footprint "eagle-import:LED0603")
      (fields (field (name "HOUSEPART") "NO"))
      (libsource (lib "eagle-import") (part "LED_SINGLE-0603"))
    )
    (comp (ref "D19")
      (value "Green")
      (footprint "eagle-import:LED0603")
      (fields (field (name "HOUSEPART") "NO"))
      (libsource (lib "eagle-import") (part "LED_SINGLE-0603"))
    )
    (comp (ref "D20")
      (value "Red")
      (footprint "eagle-import:LED0603")
      (fields (field (name "HOUSEPART") "NO"))
      (libsource (lib "eagle-import") (part "LED_SINGLE-0603"))
    )
    (comp (ref "D21")
      (value "Blue")
      (footprint "eagle-import:LED0603")
      (fields (field (name "HOUSEPART") "NO"))
      (libsource (lib "eagle-import") (part "LED_SINGLE-0603"))
    )
    (comp (ref "F3")
      (value "40A")
      (footprint "eagle-import:FUSE_ATO")
      (fields (field (name "MFG") "Littelfuse") (field (name "PARTNO") "178.6165.0001"))
      (libsource (lib "eagle-import") (part "FUSE"))
    )
    (comp (ref "JP1")
      (value "10x1F-H8.5")
      (footprint "eagle-import:1X10")
      (libsource (lib "eagle-import") (part "PINHD-1X10_ARD"))
    )
    (comp (ref "JP2")
      (value "JP1E")
      (footprint "eagle-import:JP1")
      (libsource (lib "eagle-import") (part "JP1E"))
    )
    (comp (ref "POWER")
      (value "8x1F-H8.5")
      (footprint "eagle-import:1X08")
      (libsource (lib "eagle-import") (part "PINHD-1X8"))
    )
    (comp (ref "PWML")
      (value "8x1F-H8.5")
      (footprint "eagle-import:1X08")
      (libsource (lib "eagle-import") (part "PINHD-1X8"))
    )
    (comp (ref "Q9")
      (value "N-CHANNEL_FET_SOT-23-3")
      (footprint "eagle-import:SOT-23-3")
      (fields (field (name "HOUSEPART") "NO"))
      (libsource (lib "eagle-import") (part "N-CHANNEL_FET_SOT-23-3"))
    )
    (comp (ref "Q10")
      (value "RE1C002UN")
      (footprint "eagle-import:EMT3F")
      (libsource (lib "eagle-import") (part "RE1C002UN"))
    )
    (comp (ref "R97")
      (value "1k")
      (footprint "eagle-import:R0402")
      (libsource (lib "eagle-import") (part "RESISTOR_0402"))
    )
    (comp (ref "R98")
      (value "1k")
      (footprint "eagle-import:R0402")
      (libsource (lib "eagle-import") (part "RESISTOR_0402"))
    )
    (comp (ref "R99")
      (value "1k")
      (footprint "eagle-import:R0402")
      (libsource (lib "eagle-import") (part "RESISTOR_0402"))
    )
    (comp (ref "R100")
      (value "1k")
      (footprint "eagle-import:R0402")
      (libsource (lib "eagle-import") (part "RESISTOR_0402"))
    )
    (comp (ref "R101")
      (value ".3")
      (footprint "eagle-import:R0402")
      (libsource (lib "eagle-import") (part "RESISTOR_0402"))
    )
    (comp (ref "R102")
      (value "120")
      (footprint "eagle-import:R0402")
      (libsource (lib "eagle-import") (part "RESISTOR_0402"))
    )
    (comp (ref "R103")
      (value "1k")
      (footprint "eagle-import:R0402")
      (libsource (lib "eagle-import") (part "RESISTOR_0402"))
    )
    (comp (ref "R104")
      (value "10k")
      (footprint "eagle-import:R0402")
      (libsource (lib "eagle-import") (part "RESISTOR_0402"))
    )
    (comp (ref "R105")
      (value "47k")
      (footprint "eagle-import:R0402")
      (libsource (lib "eagle-import") (part "RESISTOR_0402"))
    )
    (comp (ref "R106")
      (value "0")
      (footprint "eagle-import:R0402")
      (libsource (lib "eagle-import") (part "RESISTOR_0402"))
    )
    (comp (ref "R107")
      (value "0")
      (footprint "eagle-import:R0402")
      (libsource (lib "eagle-import") (part "RESISTOR_0402"))
    )
    (comp (ref "R108")
      (value "0")
      (footprint "eagle-import:R0402")
      (libsource (lib "eagle-import") (part "RESISTOR_0402"))
    )
    (comp (ref "R109")
      (value "0")
      (footprint "eagle-import:R0402")
      (libsource (lib "eagle-import") (part "RESISTOR_0402"))
    )
    (comp (ref "R110")
      (value "0")
      (footprint "eagle-import:R0402")
      (libsource (lib "eagle-import") (part "RESISTOR_0402"))
    )
    (comp (ref "R111")
      (value "DNP")
      (footprint "eagle-import:R0402")
      (libsource (lib "eagle-import") (part "RESISTOR_0402"))
    )
    (comp (ref "R112")
      (value "DNP")
      (footprint "eagle-import:R0402")
      (libsource (lib "eagle-import") (part "RESISTOR_0402"))
    )
    (comp (ref "R113")
      (value "DNP")
      (footprint "eagle-import:R0402")
      (libsource (lib "eagle-import") (part "RESISTOR_0402"))
    )
    (comp (ref "R114")
      (value "DNP")
      (footprint "eagle-import:R0402")
      (libsource (lib "eagle-import") (part "RESISTOR_0402"))
    )
    (comp (ref "R115")
      (value "DNP")
      (footprint "eagle-import:R0402")
      (libsource (lib "eagle-import") (part "RESISTOR_0402"))
    )
    (comp (ref "RELAY1")
      (value "RELAY_DPDT")
      (footprint "eagle-import:KEMET_EE2")
      (fields (field (name "PARTNO") "EE2-5NU-L"))
      (libsource (lib "eagle-import") (part "RELAY_DPDT"))
    )
    (comp (ref "RELAY2")
      (value "RELAY_BOM")
      (footprint "eagle-import:VCF4_RELAY")
      (fields (field (name "MFG") "TE") (field (name "PARTNO") "1432868-1"))
      (libsource (lib "eagle-import") (part "RELAY_BOM"))
    )
    (comp (ref "RELAY3")
      (value "RELAY_VF4")
      (footprint "eagle-import:VCF4-SOCKET")
      (fields (field (name "MFG") "TE") (field (name "PARTNO") "VCF4-1000"))
      (libsource (lib "eagle-import") (part "RELAY_VF4"))
    )
    (comp (ref "U13")
      (value "TL750M")
      (footprint "eagle-import:TO-263")
      (libsource (lib "eagle-import") (part "TL750M"))
    )
    (comp (ref "U14")
      (value "MCP2551")
      (footprint "eagle-import:SOIC8-6.0")
      (libsource (lib "eagle-import") (part "MCP2551-SOIC8"))
    )
    (comp (ref "U15")
      (value "MCP2515")
      (footprint "eagle-import:SOIC18")
      (libsource (lib "eagle-import") (part "MCP2515-SOIC18"))
    )
    (comp (ref "X1")
      (value "16MHz")
      (footprint "eagle-import:HC49UP")
      (libsource (lib "eagle-import") (part "CRYSTAL-HC49UP"))
    )
    (comp (ref "XIO")
      (value "18x2F-H8.5")
      (footprint "eagle-import:2X18")
      (libsource (lib "eagle-import") (part "PINHD-2X18"))
    )
    (comp (ref "C13")
      (value "1u")
      (footprint "eagle-import:C1206")
      (libsource (lib "eagle-import") (part "CAPACITOR_NP_1206"))
    )
    (comp (ref "C14")
      (value "1u")
      (footprint "eagle-import:C1206")
      (libsource (lib "eagle-import") (part "CAPACITOR_NP_1206"))
    )
    (comp (ref "C15")
      (value "1u")
      (footprint "eagle-import:C1206")
      (libsource (lib "eagle-import") (part "CAPACITOR_NP_1206"))
    )
    (comp (ref "C16")
      (value "1u")
      (footprint "eagle-import:C1206")
      (libsource (lib "eagle-import") (part "CAPACITOR_NP_1206"))
    )
    (comp (ref "C17")
      (value "1u")
      (footprint "eagle-import:C1206")
      (libsource (lib "eagle-import") (part "CAPACITOR_NP_1206"))
    )
    (comp (ref "C18")
      (value "1u")
      (footprint "eagle-import:C1206")
      (libsource (lib "eagle-import") (part "CAPACITOR_NP_1206"))
    )
    (comp (ref "C19")
      (value "0.1u")
      (footprint "eagle-import:C0805")
      (libsource (lib "eagle-import") (part "CAPACITOR_NP_0805"))
    )
    (comp (ref "C20")
      (value "0.1u")
      (footprint "eagle-import:C0805")
      (libsource (lib "eagle-import") (part "CAPACITOR_NP_0805"))
    )
    (comp (ref "C21")
      (value "0.1u")
      (footprint "eagle-import:C0805")
      (libsource (lib "eagle-import") (part "CAPACITOR_NP_0805"))
    )
    (comp (ref "C22")
      (value "0.1u")
      (footprint "eagle-import:C0805")
      (libsource (lib "eagle-import") (part "CAPACITOR_NP_0805"))
    )
    (comp (ref "C23")
      (value "0.1u")
      (footprint "eagle-import:C0805")
      (libsource (lib "eagle-import") (part "CAPACITOR_NP_0805"))
    )
    (comp (ref "C24")
      (value "0.1u")
      (footprint "eagle-import:C0805")
      (libsource (lib "eagle-import") (part "CAPACITOR_NP_0805"))
    )
    (comp (ref "CON5")
      (value "CON23.5MM")
      (footprint "eagle-import:PHOENIX_2_45")
      (libsource (lib "eagle-import") (part "CON23.5MM"))
    )
    (comp (ref "CON6")
      (value "CON23.5MM")
      (footprint "eagle-import:PHOENIX_2_45")
      (libsource (lib "eagle-import") (part "CON23.5MM"))
    )
    (comp (ref "CON7")
      (value "CON23.5MM")
      (footprint "eagle-import:PHOENIX_2_45")
      (libsource (lib "eagle-import") (part "CON23.5MM"))
    )
    (comp (ref "CON8")
      (value "CON23.5MM")
      (footprint "eagle-import:PHOENIX_2_45")
      (libsource (lib "eagle-import") (part "CON23.5MM"))
    )
    (comp (ref "D5")
      (value "DIODES_SMA")
      (footprint "eagle-import:SMA")
      (fields (field (name "HOUSEPART") "NO"))
      (libsource (lib "eagle-import") (part "DIODES_SMA"))
    )
    (comp (ref "D6")
      (value "DIODES_SMA")
      (footprint "eagle-import:SMA")
      (fields (field (name "HOUSEPART") "NO"))
      (libsource (lib "eagle-import") (part "DIODES_SMA"))
    )
    (comp (ref "D7")
      (value "DIODES_SMA")
      (footprint "eagle-import:SMA")
      (fields (field (name "HOUSEPART") "NO"))
      (libsource (lib "eagle-import") (part "DIODES_SMA"))
    )
    (comp (ref "D8")
      (value "DIODES_SMA")
      (footprint "eagle-import:SMA")
      (fields (field (name "HOUSEPART") "NO"))
      (libsource (lib "eagle-import") (part "DIODES_SMA"))
    )
    (comp (ref "F2")
      (value "20A")
      (footprint "eagle-import:FUSE_ATO")
      (fields (field (name "MFG") "Littelfuse") (field (name "PARTNO") "178.6165.0001"))
      (libsource (lib "eagle-import") (part "FUSE"))
    )
    (comp (ref "L5")
      (value "2.2u")
      (footprint "eagle-import:SRP7050")
      (fields (field (name "MFG") "Bourns") (field (name "PARTNO") "SRP7050TA-2R2M"))
      (libsource (lib "eagle-import") (part "INDUCTORSRP7050"))
    )
    (comp (ref "L6")
      (value "2.2u")
      (footprint "eagle-import:SRP7050")
      (fields (field (name "MFG") "Bourns") (field (name "PARTNO") "SRP7050TA-2R2M"))
      (libsource (lib "eagle-import") (part "INDUCTORSRP7050"))
    )
    (comp (ref "L7")
      (value "2.2u")
      (footprint "eagle-import:SRP7050")
      (fields (field (name "MFG") "Bourns") (field (name "PARTNO") "SRP7050TA-2R2M"))
      (libsource (lib "eagle-import") (part "INDUCTORSRP7050"))
    )
    (comp (ref "L8")
      (value "2.2u")
      (footprint "eagle-import:SRP7050")
      (fields (field (name "MFG") "Bourns") (field (name "PARTNO") "SRP7050TA-2R2M"))
      (libsource (lib "eagle-import") (part "INDUCTORSRP7050"))
    )
    (comp (ref "Q5")
      (value "N-FET-TO263NEXFET")
      (footprint "eagle-import:SON8-DQJ")
      (libsource (lib "eagle-import") (part "N-FET-TO263NEXFET"))
    )
    (comp (ref "Q6")
      (value "N-FET-TO263NEXFET")
      (footprint "eagle-import:SON8-DQJ")
      (libsource (lib "eagle-import") (part "N-FET-TO263NEXFET"))
    )
    (comp (ref "Q7")
      (value "N-FET-TO263NEXFET")
      (footprint "eagle-import:SON8-DQJ")
      (libsource (lib "eagle-import") (part "N-FET-TO263NEXFET"))
    )
    (comp (ref "Q8")
      (value "N-FET-TO263NEXFET")
      (footprint "eagle-import:SON8-DQJ")
      (libsource (lib "eagle-import") (part "N-FET-TO263NEXFET"))
    )
    (comp (ref "R17")
      (value "10k")
      (footprint "eagle-import:R0402")
      (libsource (lib "eagle-import") (part "RESISTOR_0402"))
    )
    (comp (ref "R18")
      (value "10k")
      (footprint "eagle-import:R0402")
      (libsource (lib "eagle-import") (part "RESISTOR_0402"))
    )
    (comp (ref "R19")
      (value "10k")
      (footprint "eagle-import:R0402")
      (libsource (lib "eagle-import") (part "RESISTOR_0402"))
    )
    (comp (ref "R20")
      (value "10k")
      (footprint "eagle-import:R0402")
      (libsource (lib "eagle-import") (part "RESISTOR_0402"))
    )
    (comp (ref "R21")
      (value "100")
      (footprint "eagle-import:R0805")
      (libsource (lib "eagle-import") (part "RESISTOR_0805"))
    )
    (comp (ref "R22")
      (value "100")
      (footprint "eagle-import:R0805")
      (libsource (lib "eagle-import") (part "RESISTOR_0805"))
    )
    (comp (ref "R23")
      (value "100")
      (footprint "eagle-import:R0805")
      (libsource (lib "eagle-import") (part "RESISTOR_0805"))
    )
    (comp (ref "R24")
      (value "100")
      (footprint "eagle-import:R0805")
      (libsource (lib "eagle-import") (part "RESISTOR_0805"))
    )
    (comp (ref "R25")
      (value ".02")
      (footprint "eagle-import:R1206")
      (libsource (lib "eagle-import") (part "RESISTOR_1206"))
    )
    (comp (ref "R26")
      (value ".02")
      (footprint "eagle-import:R1206")
      (libsource (lib "eagle-import") (part "RESISTOR_1206"))
    )
    (comp (ref "R27")
      (value ".02")
      (footprint "eagle-import:R1206")
      (libsource (lib "eagle-import") (part "RESISTOR_1206"))
    )
    (comp (ref "R28")
      (value ".02")
      (footprint "eagle-import:R1206")
      (libsource (lib "eagle-import") (part "RESISTOR_1206"))
    )
    (comp (ref "R29")
      (value "0")
      (footprint "eagle-import:R0805")
      (libsource (lib "eagle-import") (part "RESISTOR_0805"))
    )
    (comp (ref "R30")
      (value "0")
      (footprint "eagle-import:R0805")
      (libsource (lib "eagle-import") (part "RESISTOR_0805"))
    )
    (comp (ref "R31")
      (value "0")
      (footprint "eagle-import:R0805")
      (libsource (lib "eagle-import") (part "RESISTOR_0805"))
    )
    (comp (ref "R32")
      (value "0")
      (footprint "eagle-import:R0805")
      (libsource (lib "eagle-import") (part "RESISTOR_0805"))
    )
    (comp (ref "U3")
      (value "UCC27524")
      (footprint "eagle-import:SOIC-8")
      (libsource (lib "eagle-import") (part "UCC27524"))
    )
    (comp (ref "U4")
      (value "UCC27524")
      (footprint "eagle-import:SOIC-8")
      (libsource (lib "eagle-import") (part "UCC27524"))
    )
    (comp (ref "C25")
      (value "100p")
      (footprint "eagle-import:C0402")
      (libsource (lib "eagle-import") (part "CAPACITOR_NP_0402"))
    )
    (comp (ref "C26")
      (value ".1u")
      (footprint "eagle-import:C0402")
      (libsource (lib "eagle-import") (part "CAPACITOR_NP_0402"))
    )
    (comp (ref "C27")
      (value ".1u")
      (footprint "eagle-import:C0402")
      (libsource (lib "eagle-import") (part "CAPACITOR_NP_0402"))
    )
    (comp (ref "C28")
      (value "100p")
      (footprint "eagle-import:C0402")
      (libsource (lib "eagle-import") (part "CAPACITOR_NP_0402"))
    )
    (comp (ref "C29")
      (value ".1u")
      (footprint "eagle-import:C0402")
      (libsource (lib "eagle-import") (part "CAPACITOR_NP_0402"))
    )
    (comp (ref "C30")
      (value ".1u")
      (footprint "eagle-import:C0402")
      (libsource (lib "eagle-import") (part "CAPACITOR_NP_0402"))
    )
    (comp (ref "C31")
      (value "100p")
      (footprint "eagle-import:C0402")
      (libsource (lib "eagle-import") (part "CAPACITOR_NP_0402"))
    )
    (comp (ref "C32")
      (value ".1u")
      (footprint "eagle-import:C0402")
      (libsource (lib "eagle-import") (part "CAPACITOR_NP_0402"))
    )
    (comp (ref "C33")
      (value ".1u")
      (footprint "eagle-import:C0402")
      (libsource (lib "eagle-import") (part "CAPACITOR_NP_0402"))
    )
    (comp (ref "C34")
      (value "100p")
      (footprint "eagle-import:C0402")
      (libsource (lib "eagle-import") (part "CAPACITOR_NP_0402"))
    )
    (comp (ref "C35")
      (value ".1u")
      (footprint "eagle-import:C0402")
      (libsource (lib "eagle-import") (part "CAPACITOR_NP_0402"))
    )
    (comp (ref "C36")
      (value ".1u")
      (footprint "eagle-import:C0402")
      (libsource (lib "eagle-import") (part "CAPACITOR_NP_0402"))
    )
    (comp (ref "D9")
      (value "DIODES_SOD-123")
      (footprint "eagle-import:SOD-123")
      (fields (field (name "HOUSEPART") "NO"))
      (libsource (lib "eagle-import") (part "DIODES_SOD-123"))
    )
    (comp (ref "D10")
      (value "DIODES_SOD-123")
      (footprint "eagle-import:SOD-123")
      (fields (field (name "HOUSEPART") "NO"))
      (libsource (lib "eagle-import") (part "DIODES_SOD-123"))
    )
    (comp (ref "D11")
      (value "DIODES_SOD-123")
      (footprint "eagle-import:SOD-123")
      (fields (field (name "HOUSEPART") "NO"))
      (libsource (lib "eagle-import") (part "DIODES_SOD-123"))
    )
    (comp (ref "D12")
      (value "DIODES_SOD-123")
      (footprint "eagle-import:SOD-123")
      (fields (field (name "HOUSEPART") "NO"))
      (libsource (lib "eagle-import") (part "DIODES_SOD-123"))
    )
    (comp (ref "R33")
      (value "100k")
      (footprint "eagle-import:R0402")
      (libsource (lib "eagle-import") (part "RESISTOR_0402"))
    )
    (comp (ref "R34")
      (value "100k")
      (footprint "eagle-import:R0402")
      (libsource (lib "eagle-import") (part "RESISTOR_0402"))
    )
    (comp (ref "R35")
      (value "100k")
      (footprint "eagle-import:R0402")
      (libsource (lib "eagle-import") (part "RESISTOR_0402"))
    )
    (comp (ref "R36")
      (value "1k")
      (footprint "eagle-import:R0402")
      (libsource (lib "eagle-import") (part "RESISTOR_0402"))
    )
    (comp (ref "R37")
      (value "1k")
      (footprint "eagle-import:R0402")
      (libsource (lib "eagle-import") (part "RESISTOR_0402"))
    )
    (comp (ref "R38")
      (value "1k")
      (footprint "eagle-import:R0402")
      (libsource (lib "eagle-import") (part "RESISTOR_0402"))
    )
    (comp (ref "R39")
      (value "1k")
      (footprint "eagle-import:R0402")
      (libsource (lib "eagle-import") (part "RESISTOR_0402"))
    )
    (comp (ref "R40")
      (value "1k")
      (footprint "eagle-import:R0402")
      (libsource (lib "eagle-import") (part "RESISTOR_0402"))
    )
    (comp (ref "R41")
      (value "1k")
      (footprint "eagle-import:R0402")
      (libsource (lib "eagle-import") (part "RESISTOR_0402"))
    )
    (comp (ref "R42")
      (value "1k")
      (footprint "eagle-import:R0402")
      (libsource (lib "eagle-import") (part "RESISTOR_0402"))
    )
    (comp (ref "R43")
      (value "1k")
      (footprint "eagle-import:R0402")
      (libsource (lib "eagle-import") (part "RESISTOR_0402"))
    )
    (comp (ref "R44")
      (value "1k")
      (footprint "eagle-import:R0402")
      (libsource (lib "eagle-import") (part "RESISTOR_0402"))
    )
    (comp (ref "R45")
      (value "100k")
      (footprint "eagle-import:R0402")
      (libsource (lib "eagle-import") (part "RESISTOR_0402"))
    )
    (comp (ref "R46")
      (value "100k")
      (footprint "eagle-import:R0402")
      (libsource (lib "eagle-import") (part "RESISTOR_0402"))
    )
    (comp (ref "R47")
      (value "100k")
      (footprint "eagle-import:R0402")
      (libsource (lib "eagle-import") (part "RESISTOR_0402"))
    )
    (comp (ref "R48")
      (value "100k")
      (footprint "eagle-import:R0402")
      (libsource (lib "eagle-import") (part "RESISTOR_0402"))
    )
    (comp (ref "R49")
      (value "100k")
      (footprint "eagle-import:R0402")
      (libsource (lib "eagle-import") (part "RESISTOR_0402"))
    )
    (comp (ref "R50")
      (value "100k")
      (footprint "eagle-import:R0402")
      (libsource (lib "eagle-import") (part "RESISTOR_0402"))
    )
    (comp (ref "R51")
      (value "1k")
      (footprint "eagle-import:R0402")
      (libsource (lib "eagle-import") (part "RESISTOR_0402"))
    )
    (comp (ref "R52")
      (value "1k")
      (footprint "eagle-import:R0402")
      (libsource (lib "eagle-import") (part "RESISTOR_0402"))
    )
    (comp (ref "R53")
      (value "1k")
      (footprint "eagle-import:R0402")
      (libsource (lib "eagle-import") (part "RESISTOR_0402"))
    )
    (comp (ref "R54")
      (value "1k")
      (footprint "eagle-import:R0402")
      (libsource (lib "eagle-import") (part "RESISTOR_0402"))
    )
    (comp (ref "R55")
      (value "1k")
      (footprint "eagle-import:R0402")
      (libsource (lib "eagle-import") (part "RESISTOR_0402"))
    )
    (comp (ref "R56")
      (value "1k")
      (footprint "eagle-import:R0402")
      (libsource (lib "eagle-import") (part "RESISTOR_0402"))
    )
    (comp (ref "R57")
      (value "100k")
      (footprint "eagle-import:R0402")
      (libsource (lib "eagle-import") (part "RESISTOR_0402"))
    )
    (comp (ref "R58")
      (value "1k")
      (footprint "eagle-import:R0402")
      (libsource (lib "eagle-import") (part "RESISTOR_0402"))
    )
    (comp (ref "R59")
      (value "1k")
      (footprint "eagle-import:R0402")
      (libsource (lib "eagle-import") (part "RESISTOR_0402"))
    )
    (comp (ref "R60")
      (value "1k")
      (footprint "eagle-import:R0402")
      (libsource (lib "eagle-import") (part "RESISTOR_0402"))
    )
    (comp (ref "R61")
      (value "100k")
      (footprint "eagle-import:R0402")
      (libsource (lib "eagle-import") (part "RESISTOR_0402"))
    )
    (comp (ref "R62")
      (value "100k")
      (footprint "eagle-import:R0402")
      (libsource (lib "eagle-import") (part "RESISTOR_0402"))
    )
    (comp (ref "R63")
      (value "1k")
      (footprint "eagle-import:R0402")
      (libsource (lib "eagle-import") (part "RESISTOR_0402"))
    )
    (comp (ref "R64")
      (value "1k")
      (footprint "eagle-import:R0402")
      (libsource (lib "eagle-import") (part "RESISTOR_0402"))
    )
    (comp (ref "U5")
      (value "OPA170")
      (footprint "eagle-import:SOT-23-5")
      (libsource (lib "eagle-import") (part "OPA170"))
    )
    (comp (ref "U6")
      (value "OPA170")
      (footprint "eagle-import:SOT-23-5")
      (libsource (lib "eagle-import") (part "OPA170"))
    )
    (comp (ref "U7")
      (value "OPA170")
      (footprint "eagle-import:SOT-23-5")
      (libsource (lib "eagle-import") (part "OPA170"))
    )
    (comp (ref "U8")
      (value "OPA170")
      (footprint "eagle-import:SOT-23-5")
      (libsource (lib "eagle-import") (part "OPA170"))
    )
  )
  (nets
    (net (code "1") (name "+3V3") (class "Default")
      (node (ref "POWER") (pin "4") (pinfunction "4_4") (pintype "passive"))
    )
    (net (code "2") (name "+5V") (class "Default")
      (node (ref "C26") (pin "P$1") (pinfunction "P$1_P$1") (pintype "passive"))
      (node (ref "C29") (pin "P$1") (pinfunction "P$1_P$1") (pintype "passive"))
      (node (ref "C32") (pin "P$1") (pinfunction "P$1_P$1") (pintype "passive"))
      (node (ref "C35") (pin "P$1") (pinfunction "P$1_P$1") (pintype "passive"))
      (node (ref "C38") (pin "P$1") (pinfunction "P$1_P$1") (pintype "passive"))
      (node (ref "C41") (pin "P$1") (pinfunction "P$1_P$1") (pintype "passive"))
      (node (ref "C44") (pin "P$1") (pinfunction "P$1_P$1") (pintype "passive"))
      (node (ref "C47") (pin "P$1") (pinfunction "P$1_P$1") (pintype "passive"))
      (node (ref "C49") (pin "P$1") (pinfunction "P$1_P$1") (pintype "passive"))
      (node (ref "C51") (pin "P$1") (pinfunction "P$1_P$1") (pintype "passive"))
      (node (ref "CON12") (pin "P$1") (pinfunction "P$1_P$1") (pintype "bidirectional"))
      (node (ref "POWER") (pin "2") (pinfunction "2_2") (pintype "passive"))
      (node (ref "POWER") (pin "5") (pinfunction "5_5") (pintype "passive"))
      (node (ref "R100") (pin "P$2") (pinfunction "P$2_P$2") (pintype "passive"))
      (node (ref "R101") (pin "P$1") (pinfunction "P$1_P$1") (pintype "passive"))
      (node (ref "R103") (pin "P$2") (pinfunction "P$2_P$2") (pintype "passive"))
      (node (ref "R104") (pin "P$1") (pinfunction "P$1_P$1") (pintype "passive"))
      (node (ref "R97") (pin "P$2") (pinfunction "P$2_P$2") (pintype "passive"))
      (node (ref "R98") (pin "P$2") (pinfunction "P$2_P$2") (pintype "passive"))
      (node (ref "R99") (pin "P$2") (pinfunction "P$2_P$2") (pintype "passive"))
      (node (ref "RELAY1") (pin "P$1") (pinfunction "P$1_P$1") (pintype "bidirectional"))
      (node (ref "U10") (pin "P$5") (pinfunction "V+_P$5") (pintype "bidirectional"))
      (node (ref "U11") (pin "P$5") (pinfunction "V+_P$5") (pintype "bidirectional"))
      (node (ref "U12") (pin "P$5") (pinfunction "V+_P$5") (pintype "bidirectional"))
      (node (ref "U13") (pin "P$3") (pinfunction "VOUT_P$3") (pintype "bidirectional"))
      (node (ref "U14") (pin "3") (pinfunction "VDD_3") (pintype "bidirectional"))
      (node (ref "U15") (pin "18") (pinfunction "VDD_18") (pintype "power_in"))
      (node (ref "U5") (pin "P$5") (pinfunction "V+_P$5") (pintype "bidirectional"))
      (node (ref "U6") (pin "P$5") (pinfunction "V+_P$5") (pintype "bidirectional"))
      (node (ref "U7") (pin "P$5") (pinfunction "V+_P$5") (pintype "bidirectional"))
      (node (ref "U8") (pin "P$5") (pinfunction "V+_P$5") (pintype "bidirectional"))
      (node (ref "U9") (pin "P$5") (pinfunction "V+_P$5") (pintype "bidirectional"))
    )
    (net (code "3") (name "ADC8") (class "Default")
      (node (ref "ADCH") (pin "1") (pinfunction "1_1") (pintype "passive"))
    )
    (net (code "4") (name "ADC9") (class "Default")
      (node (ref "ADCH") (pin "2") (pinfunction "2_2") (pintype "passive"))
      (node (ref "R106") (pin "P$1") (pinfunction "P$1_P$1") (pintype "passive"))
      (node (ref "R115") (pin "P$1") (pinfunction "P$1_P$1") (pintype "passive"))
    )
    (net (code "5") (name "ADC10") (class "Default")
      (node (ref "ADCH") (pin "3") (pinfunction "3_3") (pintype "passive"))
      (node (ref "R107") (pin "P$1") (pinfunction "P$1_P$1") (pintype "passive"))
      (node (ref "R114") (pin "P$1") (pinfunction "P$1_P$1") (pintype "passive"))
    )
    (net (code "6") (name "ADC11") (class "Default")
      (node (ref "ADCH") (pin "4") (pinfunction "4_4") (pintype "passive"))
      (node (ref "R108") (pin "P$1") (pinfunction "P$1_P$1") (pintype "passive"))
      (node (ref "R113") (pin "P$1") (pinfunction "P$1_P$1") (pintype "passive"))
    )
    (net (code "7") (name "ADC12") (class "Default")
      (node (ref "ADCH") (pin "5") (pinfunction "5_5") (pintype "passive"))
    )
    (net (code "8") (name "ADC13") (class "Default")
      (node (ref "ADCH") (pin "6") (pinfunction "6_6") (pintype "passive"))
      (node (ref "R109") (pin "P$1") (pinfunction "P$1_P$1") (pintype "passive"))
      (node (ref "R112") (pin "P$1") (pinfunction "P$1_P$1") (pintype "passive"))
    )
    (net (code "9") (name "ADC14") (class "Default")
      (node (ref "ADCH") (pin "7") (pinfunction "7_7") (pintype "passive"))
      (node (ref "R110") (pin "P$1") (pinfunction "P$1_P$1") (pintype "passive"))
      (node (ref "R111") (pin "P$1") (pinfunction "P$1_P$1") (pintype "passive"))
    )
    (net (code "10") (name "ADC15") (class "Default")
      (node (ref "ADCH") (pin "8") (pinfunction "8_8") (pintype "passive"))
    )
    (net (code "11") (name "AREF") (class "Default")
      (node (ref "JP1") (pin "3") (pinfunction "3_3") (pintype "passive"))
    )
    (net (code "12") (name "CANH") (class "Default")
      (node (ref "CON14") (pin "P$1") (pinfunction "P$1_P$1") (pintype "bidirectional"))
      (node (ref "JP2") (pin "1") (pinfunction "1_1") (pintype "passive"))
      (node (ref "U14") (pin "7") (pinfunction "CANH_7") (pintype "bidirectional"))
    )
    (net (code "13") (name "CANL") (class "Default")
      (node (ref "CON14") (pin "P$2") (pinfunction "P$2_P$2") (pintype "bidirectional"))
      (node (ref "R102") (pin "P$1") (pinfunction "P$1_P$1") (pintype "passive"))
      (node (ref "U14") (pin "6") (pinfunction "CANL_6") (pintype "bidirectional"))
    )
    (net (code "14") (name "CS") (class "Default")
      (node (ref "U15") (pin "16") (pinfunction "~{CS}_16") (pintype "input"))
      (node (ref "XIO") (pin "34") (pinfunction "34_34") (pintype "passive"))
    )
    (net (code "15") (name "GND") (class "Default")
      (node (ref "C1") (pin "P$2") (pinfunction "P$2_P$2") (pintype "passive"))
      (node (ref "C10") (pin "P$2") (pinfunction "P$2_P$2") (pintype "passive"))
      (node (ref "C11") (pin "P$2") (pinfunction "P$2_P$2") (pintype "passive"))
      (node (ref "C12") (pin "P$2") (pinfunction "P$2_P$2") (pintype "passive"))
      (node (ref "C13") (pin "P$2") (pinfunction "P$2_P$2") (pintype "passive"))
      (node (ref "C14") (pin "P$2") (pinfunction "P$2_P$2") (pintype "passive"))
      (node (ref "C15") (pin "P$2") (pinfunction "P$2_P$2") (pintype "passive"))
      (node (ref "C16") (pin "P$2") (pinfunction "P$2_P$2") (pintype "passive"))
      (node (ref "C17") (pin "P$2") (pinfunction "P$2_P$2") (pintype "passive"))
      (node (ref "C18") (pin "P$2") (pinfunction "P$2_P$2") (pintype "passive"))
      (node (ref "C2") (pin "P$2") (pinfunction "P$2_P$2") (pintype "passive"))
      (node (ref "C23") (pin "P$2") (pinfunction "P$2_P$2") (pintype "passive"))
      (node (ref "C24") (pin "P$2") (pinfunction "P$2_P$2") (pintype "passive"))
      (node (ref "C26") (pin "P$2") (pinfunction "P$2_P$2") (pintype "passive"))
      (node (ref "C27") (pin "P$2") (pinfunction "P$2_P$2") (pintype "passive"))
      (node (ref "C29") (pin "P$2") (pinfunction "P$2_P$2") (pintype "passive"))
      (node (ref "C30") (pin "P$2") (pinfunction "P$2_P$2") (pintype "passive"))
      (node (ref "C32") (pin "P$2") (pinfunction "P$2_P$2") (pintype "passive"))
      (node (ref "C33") (pin "P$2") (pinfunction "P$2_P$2") (pintype "passive"))
      (node (ref "C35") (pin "P$2") (pinfunction "P$2_P$2") (pintype "passive"))
      (node (ref "C36") (pin "P$2") (pinfunction "P$2_P$2") (pintype "passive"))
      (node (ref "C38") (pin "P$2") (pinfunction "P$2_P$2") (pintype "passive"))
      (node (ref "C39") (pin "P$2") (pinfunction "P$2_P$2") (pintype "passive"))
      (node (ref "C41") (pin "P$2") (pinfunction "P$2_P$2") (pintype "passive"))
      (node (ref "C42") (pin "P$2") (pinfunction "P$2_P$2") (pintype "passive"))
      (node (ref "C44") (pin "P$2") (pinfunction "P$2_P$2") (pintype "passive"))
      (node (ref "C45") (pin "P$2") (pinfunction "P$2_P$2") (pintype "passive"))
      (node (ref "C47") (pin "P$2") (pinfunction "P$2_P$2") (pintype "passive"))
      (node (ref "C48") (pin "P$2") (pinfunction "P$2_P$2") (pintype "passive"))
      (node (ref "C49") (pin "P$2") (pinfunction "P$2_P$2") (pintype "passive"))
      (node (ref "C5") (pin "P$2") (pinfunction "P$2_P$2") (pintype "passive"))
      (node (ref "C50") (pin "P$2") (pinfunction "P$2_P$2") (pintype "passive"))
      (node (ref "C51") (pin "P$2") (pinfunction "P$2_P$2") (pintype "passive"))
      (node (ref "C52") (pin "P$1") (pinfunction "P$1_P$1") (pintype "passive"))
      (node (ref "C53") (pin "P$1") (pinfunction "P$1_P$1") (pintype "passive"))
      (node (ref "C6") (pin "P$2") (pinfunction "P$2_P$2") (pintype "passive"))
      (node (ref "C9") (pin "P$2") (pinfunction "P$2_P$2") (pintype "passive"))
      (node (ref "CON11") (pin "P$3") (pinfunction "P$2_P$3") (pintype "bidirectional"))
      (node (ref "CON11") (pin "P$4") (pinfunction "P$2_P$4") (pintype "bidirectional"))
      (node (ref "CON12") (pin "P$2") (pinfunction "P$2_P$2") (pintype "bidirectional"))
      (node (ref "CON16") (pin "P$1") (pinfunction "P$1_P$1") (pintype "bidirectional"))
      (node (ref "CON16") (pin "P$2") (pinfunction "P$1_P$2") (pintype "bidirectional"))
      (node (ref "D18") (pin "CATHODE") (pinfunction "CATHODE_CATHODE") (pintype "power_in"))
      (node (ref "JP1") (pin "4") (pinfunction "4_4") (pintype "passive"))
      (node (ref "POWER") (pin "6") (pinfunction "6_6") (pintype "passive"))
      (node (ref "POWER") (pin "7") (pinfunction "7_7") (pintype "passive"))
      (node (ref "Q10") (pin "P$2") (pinfunction "S_P$2") (pintype "passive"))
      (node (ref "Q9") (pin "P$2") (pinfunction "SOURCE_P$2") (pintype "bidirectional"))
      (node (ref "R1") (pin "P$2") (pinfunction "P$2_P$2") (pintype "passive"))
      (node (ref "R10") (pin "P$1") (pinfunction "P$1_P$1") (pintype "passive"))
      (node (ref "R105") (pin "P$2") (pinfunction "P$2_P$2") (pintype "passive"))
      (node (ref "R111") (pin "P$2") (pinfunction "P$2_P$2") (pintype "passive"))
      (node (ref "R112") (pin "P$2") (pinfunction "P$2_P$2") (pintype "passive"))
      (node (ref "R113") (pin "P$2") (pinfunction "P$2_P$2") (pintype "passive"))
      (node (ref "R114") (pin "P$2") (pinfunction "P$2_P$2") (pintype "passive"))
      (node (ref "R115") (pin "P$2") (pinfunction "P$2_P$2") (pintype "passive"))
      (node (ref "R13") (pin "P$2") (pinfunction "P$2_P$2") (pintype "passive"))
      (node (ref "R14") (pin "P$2") (pinfunction "P$2_P$2") (pintype "passive"))
      (node (ref "R15") (pin "P$1") (pinfunction "P$1_P$1") (pintype "passive"))
      (node (ref "R16") (pin "P$1") (pinfunction "P$1_P$1") (pintype "passive"))
      (node (ref "R17") (pin "P$2") (pinfunction "P$2_P$2") (pintype "passive"))
      (node (ref "R18") (pin "P$2") (pinfunction "P$2_P$2") (pintype "passive"))
      (node (ref "R19") (pin "P$2") (pinfunction "P$2_P$2") (pintype "passive"))
      (node (ref "R2") (pin "P$2") (pinfunction "P$2_P$2") (pintype "passive"))
      (node (ref "R20") (pin "P$2") (pinfunction "P$2_P$2") (pintype "passive"))
      (node (ref "R29") (pin "P$1") (pinfunction "P$1_P$1") (pintype "passive"))
      (node (ref "R30") (pin "P$1") (pinfunction "P$1_P$1") (pintype "passive"))
      (node (ref "R31") (pin "P$1") (pinfunction "P$1_P$1") (pintype "passive"))
      (node (ref "R32") (pin "P$1") (pinfunction "P$1_P$1") (pintype "passive"))
      (node (ref "R33") (pin "P$1") (pinfunction "P$1_P$1") (pintype "passive"))
      (node (ref "R34") (pin "P$1") (pinfunction "P$1_P$1") (pintype "passive"))
      (node (ref "R35") (pin "P$1") (pinfunction "P$1_P$1") (pintype "passive"))
      (node (ref "R45") (pin "P$1") (pinfunction "P$1_P$1") (pintype "passive"))
      (node (ref "R46") (pin "P$1") (pinfunction "P$1_P$1") (pintype "passive"))
      (node (ref "R47") (pin "P$1") (pinfunction "P$1_P$1") (pintype "passive"))
      (node (ref "R57") (pin "P$1") (pinfunction "P$1_P$1") (pintype "passive"))
      (node (ref "R61") (pin "P$1") (pinfunction "P$1_P$1") (pintype "passive"))
      (node (ref "R65") (pin "P$1") (pinfunction "P$1_P$1") (pintype "passive"))
      (node (ref "R66") (pin "P$1") (pinfunction "P$1_P$1") (pintype "passive"))
      (node (ref "R67") (pin "P$1") (pinfunction "P$1_P$1") (pintype "passive"))
      (node (ref "R77") (pin "P$1") (pinfunction "P$1_P$1") (pintype "passive"))
      (node (ref "R78") (pin "P$1") (pinfunction "P$1_P$1") (pintype "passive"))
      (node (ref "R79") (pin "P$1") (pinfunction "P$1_P$1") (pintype "passive"))
      (node (ref "R89") (pin "P$1") (pinfunction "P$1_P$1") (pintype "passive"))
      (node (ref "R9") (pin "P$1") (pinfunction "P$1_P$1") (pintype "passive"))
      (node (ref "R93") (pin "P$1") (pinfunction "P$1_P$1") (pintype "passive"))
      (node (ref "U1") (pin "3") (pinfunction "GND_3") (pintype "bidirectional"))
      (node (ref "U10") (pin "P$2") (pinfunction "V-_P$2") (pintype "bidirectional"))
      (node (ref "U11") (pin "P$2") (pinfunction "V-_P$2") (pintype "bidirectional"))
      (node (ref "U12") (pin "P$2") (pinfunction "V-_P$2") (pintype "bidirectional"))
      (node (ref "U13") (pin "P$2") (pinfunction "GND_P$2") (pintype "bidirectional"))
      (node (ref "U13") (pin "P$4") (pinfunction "GND_P$4") (pintype "bidirectional"))
      (node (ref "U14") (pin "2") (pinfunction "VSS_2") (pintype "bidirectional"))
      (node (ref "U15") (pin "9") (pinfunction "VSS_9") (pintype "power_in"))
      (node (ref "U2") (pin "3") (pinfunction "GND_3") (pintype "bidirectional"))
      (node (ref "U3") (pin "3") (pinfunction "GND_3") (pintype "bidirectional"))
      (node (ref "U4") (pin "3") (pinfunction "GND_3") (pintype "bidirectional"))
      (node (ref "U5") (pin "P$2") (pinfunction "V-_P$2") (pintype "bidirectional"))
      (node (ref "U6") (pin "P$2") (pinfunction "V-_P$2") (pintype "bidirectional"))
      (node (ref "U7") (pin "P$2") (pinfunction "V-_P$2") (pintype "bidirectional"))
      (node (ref "U8") (pin "P$2") (pinfunction "V-_P$2") (pintype "bidirectional"))
      (node (ref "U9") (pin "P$2") (pinfunction "V-_P$2") (pintype "bidirectional"))
      (node (ref "XIO") (pin "35") (pinfunction "35_35") (pintype "passive"))
      (node (ref "XIO") (pin "36") (pinfunction "36_36") (pintype "passive"))
    )
    (net (code "16") (name "INT") (class "Default")
      (node (ref "COMMUNICATION") (pin "1") (pinfunction "1_1") (pintype "passive"))
      (node (ref "D21") (pin "CATHODE") (pinfunction "CATHODE_CATHODE") (pintype "power_in"))
      (node (ref "U15") (pin "12") (pinfunction "~{INT}_12") (pintype "output"))
    )
    (net (code "17") (name "MISO") (class "Default")
      (node (ref "U15") (pin "15") (pinfunction "SO_15") (pintype "output"))
      (node (ref "XIO") (pin "31") (pinfunction "31_31") (pintype "passive"))
    )
    (net (code "18") (name "MOSI") (class "Default")
      (node (ref "U15") (pin "14") (pinfunction "SI_14") (pintype "input"))
      (node (ref "XIO") (pin "32") (pinfunction "32_32") (pintype "passive"))
    )
    (net (code "19") (name "Net-(C1-PadP$1)") (class "Default")
      (node (ref "C1") (pin "P$1") (pinfunction "P$1_P$1") (pintype "passive"))
      (node (ref "CON3") (pin "P$1") (pinfunction "P$1_P$1") (pintype "bidirectional"))
      (node (ref "D3") (pin "CATHODE") (pinfunction "CATHODE_CATHODE") (pintype "bidirectional"))
      (node (ref "L3") (pin "P$2") (pinfunction "P$2_P$2") (pintype "passive"))
    )
    (net (code "20") (name "Net-(C2-PadP$1)") (class "Default")
      (node (ref "C2") (pin "P$1") (pinfunction "P$1_P$1") (pintype "passive"))
      (node (ref "CON4") (pin "P$1") (pinfunction "P$1_P$1") (pintype "bidirectional"))
      (node (ref "D4") (pin "CATHODE") (pinfunction "CATHODE_CATHODE") (pintype "bidirectional"))
      (node (ref "L4") (pin "P$2") (pinfunction "P$2_P$2") (pintype "passive"))
    )
    (net (code "21") (name "Net-(C3-PadP$1)") (class "Default")
      (node (ref "C3") (pin "P$1") (pinfunction "P$1_P$1") (pintype "passive"))
      (node (ref "R3") (pin "P$2") (pinfunction "P$2_P$2") (pintype "passive"))
    )
    (net (code "22") (name "Net-(C4-PadP$1)") (class "Default")
      (node (ref "C4") (pin "P$1") (pinfunction "P$1_P$1") (pintype "passive"))
      (node (ref "R4") (pin "P$2") (pinfunction "P$2_P$2") (pintype "passive"))
    )
    (net (code "23") (name "Net-(C7-PadP$1)") (class "Default")
      (node (ref "C7") (pin "P$1") (pinfunction "P$1_P$1") (pintype "passive"))
      (node (ref "R5") (pin "P$2") (pinfunction "P$2_P$2") (pintype "passive"))
    )
    (net (code "24") (name "Net-(C8-PadP$1)") (class "Default")
      (node (ref "C8") (pin "P$1") (pinfunction "P$1_P$1") (pintype "passive"))
      (node (ref "R6") (pin "P$2") (pinfunction "P$2_P$2") (pintype "passive"))
    )
    (net (code "25") (name "Net-(C9-PadP$1)") (class "Default")
      (node (ref "C9") (pin "P$1") (pinfunction "P$1_P$1") (pintype "passive"))
      (node (ref "CON1") (pin "P$1") (pinfunction "P$1_P$1") (pintype "bidirectional"))
      (node (ref "D1") (pin "CATHODE") (pinfunction "CATHODE_CATHODE") (pintype "bidirectional"))
      (node (ref "L1") (pin "P$2") (pinfunction "P$2_P$2") (pintype "passive"))
    )
    (net (code "26") (name "Net-(C10-PadP$1)") (class "Default")
      (node (ref "C10") (pin "P$1") (pinfunction "P$1_P$1") (pintype "passive"))
      (node (ref "CON2") (pin "P$1") (pinfunction "P$1_P$1") (pintype "bidirectional"))
      (node (ref "D2") (pin "CATHODE") (pinfunction "CATHODE_CATHODE") (pintype "bidirectional"))
      (node (ref "L2") (pin "P$2") (pinfunction "P$2_P$2") (pintype "passive"))
    )
    (net (code "27") (name "Net-(C13-PadP$1)") (class "Default")
      (node (ref "C13") (pin "P$1") (pinfunction "P$1_P$1") (pintype "passive"))
      (node (ref "CON5") (pin "P$1") (pinfunction "P$1_P$1") (pintype "bidirectional"))
      (node (ref "D5") (pin "CATHODE") (pinfunction "CATHODE_CATHODE") (pintype "bidirectional"))
      (node (ref "L5") (pin "P$2") (pinfunction "P$2_P$2") (pintype "passive"))
    )
    (net (code "28") (name "Net-(C14-PadP$1)") (class "Default")
      (node (ref "C14") (pin "P$1") (pinfunction "P$1_P$1") (pintype "passive"))
      (node (ref "CON6") (pin "P$1") (pinfunction "P$1_P$1") (pintype "bidirectional"))
      (node (ref "D6") (pin "CATHODE") (pinfunction "CATHODE_CATHODE") (pintype "bidirectional"))
      (node (ref "L6") (pin "P$2") (pinfunction "P$2_P$2") (pintype "passive"))
    )
    (net (code "29") (name "Net-(C15-PadP$1)") (class "Default")
      (node (ref "C15") (pin "P$1") (pinfunction "P$1_P$1") (pintype "passive"))
      (node (ref "CON7") (pin "P$1") (pinfunction "P$1_P$1") (pintype "bidirectional"))
      (node (ref "D7") (pin "CATHODE") (pinfunction "CATHODE_CATHODE") (pintype "bidirectional"))
      (node (ref "L7") (pin "P$2") (pinfunction "P$2_P$2") (pintype "passive"))
    )
    (net (code "30") (name "Net-(C16-PadP$1)") (class "Default")
      (node (ref "C16") (pin "P$1") (pinfunction "P$1_P$1") (pintype "passive"))
      (node (ref "CON8") (pin "P$1") (pinfunction "P$1_P$1") (pintype "bidirectional"))
      (node (ref "D8") (pin "CATHODE") (pinfunction "CATHODE_CATHODE") (pintype "bidirectional"))
      (node (ref "L8") (pin "P$2") (pinfunction "P$2_P$2") (pintype "passive"))
    )
    (net (code "31") (name "Net-(C19-PadP$1)") (class "Default")
      (node (ref "C19") (pin "P$1") (pinfunction "P$1_P$1") (pintype "passive"))
      (node (ref "R21") (pin "P$2") (pinfunction "P$2_P$2") (pintype "passive"))
    )
    (net (code "32") (name "Net-(C20-PadP$1)") (class "Default")
      (node (ref "C20") (pin "P$1") (pinfunction "P$1_P$1") (pintype "passive"))
      (node (ref "R22") (pin "P$2") (pinfunction "P$2_P$2") (pintype "passive"))
    )
    (net (code "33") (name "Net-(C21-PadP$1)") (class "Default")
      (node (ref "C21") (pin "P$1") (pinfunction "P$1_P$1") (pintype "passive"))
      (node (ref "R23") (pin "P$2") (pinfunction "P$2_P$2") (pintype "passive"))
    )
    (net (code "34") (name "Net-(C22-PadP$1)") (class "Default")
      (node (ref "C22") (pin "P$1") (pinfunction "P$1_P$1") (pintype "passive"))
      (node (ref "R24") (pin "P$2") (pinfunction "P$2_P$2") (pintype "passive"))
    )
    (net (code "35") (name "Net-(C25-PadP$1)") (class "Default")
      (node (ref "C25") (pin "P$1") (pinfunction "P$1_P$1") (pintype "passive"))
      (node (ref "R36") (pin "P$2") (pinfunction "P$2_P$2") (pintype "passive"))
      (node (ref "R51") (pin "P$1") (pinfunction "P$1_P$1") (pintype "passive"))
    )
    (net (code "36") (name "Net-(C25-PadP$2)") (class "Default")
      (node (ref "C25") (pin "P$2") (pinfunction "P$2_P$2") (pintype "passive"))
      (node (ref "R37") (pin "P$2") (pinfunction "P$2_P$2") (pintype "passive"))
      (node (ref "R52") (pin "P$1") (pinfunction "P$1_P$1") (pintype "passive"))
    )
    (net (code "37") (name "Net-(C28-PadP$1)") (class "Default")
      (node (ref "C28") (pin "P$1") (pinfunction "P$1_P$1") (pintype "passive"))
      (node (ref "R38") (pin "P$2") (pinfunction "P$2_P$2") (pintype "passive"))
      (node (ref "R53") (pin "P$1") (pinfunction "P$1_P$1") (pintype "passive"))
    )
    (net (code "38") (name "Net-(C28-PadP$2)") (class "Default")
      (node (ref "C28") (pin "P$2") (pinfunction "P$2_P$2") (pintype "passive"))
      (node (ref "R39") (pin "P$2") (pinfunction "P$2_P$2") (pintype "passive"))
      (node (ref "R54") (pin "P$1") (pinfunction "P$1_P$1") (pintype "passive"))
    )
    (net (code "39") (name "Net-(C31-PadP$1)") (class "Default")
      (node (ref "C31") (pin "P$1") (pinfunction "P$1_P$1") (pintype "passive"))
      (node (ref "R40") (pin "P$2") (pinfunction "P$2_P$2") (pintype "passive"))
      (node (ref "R55") (pin "P$1") (pinfunction "P$1_P$1") (pintype "passive"))
    )
    (net (code "40") (name "Net-(C31-PadP$2)") (class "Default")
      (node (ref "C31") (pin "P$2") (pinfunction "P$2_P$2") (pintype "passive"))
      (node (ref "R41") (pin "P$2") (pinfunction "P$2_P$2") (pintype "passive"))
      (node (ref "R56") (pin "P$1") (pinfunction "P$1_P$1") (pintype "passive"))
    )
    (net (code "41") (name "Net-(C34-PadP$1)") (class "Default")
      (node (ref "C34") (pin "P$1") (pinfunction "P$1_P$1") (pintype "passive"))
      (node (ref "R58") (pin "P$2") (pinfunction "P$2_P$2") (pintype "passive"))
      (node (ref "R63") (pin "P$1") (pinfunction "P$1_P$1") (pintype "passive"))
    )
    (net (code "42") (name "Net-(C34-PadP$2)") (class "Default")
      (node (ref "C34") (pin "P$2") (pinfunction "P$2_P$2") (pintype "passive"))
      (node (ref "R59") (pin "P$2") (pinfunction "P$2_P$2") (pintype "passive"))
      (node (ref "R64") (pin "P$1") (pinfunction "P$1_P$1") (pintype "passive"))
    )
    (net (code "43") (name "Net-(C37-PadP$1)") (class "Default")
      (node (ref "C37") (pin "P$1") (pinfunction "P$1_P$1") (pintype "passive"))
      (node (ref "R68") (pin "P$2") (pinfunction "P$2_P$2") (pintype "passive"))
      (node (ref "R83") (pin "P$1") (pinfunction "P$1_P$1") (pintype "passive"))
    )
    (net (code "44") (name "Net-(C37-PadP$2)") (class "Default")
      (node (ref "C37") (pin "P$2") (pinfunction "P$2_P$2") (pintype "passive"))
      (node (ref "R69") (pin "P$2") (pinfunction "P$2_P$2") (pintype "passive"))
      (node (ref "R84") (pin "P$1") (pinfunction "P$1_P$1") (pintype "passive"))
    )
    (net (code "45") (name "Net-(C40-PadP$1)") (class "Default")
      (node (ref "C40") (pin "P$1") (pinfunction "P$1_P$1") (pintype "passive"))
      (node (ref "R70") (pin "P$2") (pinfunction "P$2_P$2") (pintype "passive"))
      (node (ref "R85") (pin "P$1") (pinfunction "P$1_P$1") (pintype "passive"))
    )
    (net (code "46") (name "Net-(C40-PadP$2)") (class "Default")
      (node (ref "C40") (pin "P$2") (pinfunction "P$2_P$2") (pintype "passive"))
      (node (ref "R71") (pin "P$2") (pinfunction "P$2_P$2") (pintype "passive"))
      (node (ref "R86") (pin "P$1") (pinfunction "P$1_P$1") (pintype "passive"))
    )
    (net (code "47") (name "Net-(C43-PadP$1)") (class "Default")
      (node (ref "C43") (pin "P$1") (pinfunction "P$1_P$1") (pintype "passive"))
      (node (ref "R72") (pin "P$2") (pinfunction "P$2_P$2") (pintype "passive"))
      (node (ref "R87") (pin "P$1") (pinfunction "P$1_P$1") (pintype "passive"))
    )
    (net (code "48") (name "Net-(C43-PadP$2)") (class "Default")
      (node (ref "C43") (pin "P$2") (pinfunction "P$2_P$2") (pintype "passive"))
      (node (ref "R73") (pin "P$2") (pinfunction "P$2_P$2") (pintype "passive"))
      (node (ref "R88") (pin "P$1") (pinfunction "P$1_P$1") (pintype "passive"))
    )
    (net (code "49") (name "Net-(C46-PadP$1)") (class "Default")
      (node (ref "C46") (pin "P$1") (pinfunction "P$1_P$1") (pintype "passive"))
      (node (ref "R90") (pin "P$2") (pinfunction "P$2_P$2") (pintype "passive"))
      (node (ref "R95") (pin "P$1") (pinfunction "P$1_P$1") (pintype "passive"))
    )
    (net (code "50") (name "Net-(C46-PadP$2)") (class "Default")
      (node (ref "C46") (pin "P$2") (pinfunction "P$2_P$2") (pintype "passive"))
      (node (ref "R91") (pin "P$2") (pinfunction "P$2_P$2") (pintype "passive"))
      (node (ref "R96") (pin "P$1") (pinfunction "P$1_P$1") (pintype "passive"))
    )
    (net (code "51") (name "Net-(C50-PadP$1)") (class "Default")
      (node (ref "C50") (pin "P$1") (pinfunction "P$1_P$1") (pintype "passive"))
      (node (ref "R101") (pin "P$2") (pinfunction "P$2_P$2") (pintype "passive"))
    )
    (net (code "52") (name "Net-(CON1-PadP$2)") (class "Default")
      (node (ref "CON1") (pin "P$2") (pinfunction "P$2_P$2") (pintype "bidirectional"))
      (node (ref "D1") (pin "ANODE") (pinfunction "ANODE_ANODE") (pintype "bidirectional"))
      (node (ref "Q1") (pin "P$5") (pinfunction "DRAIN_P$5") (pintype "bidirectional"))
      (node (ref "Q1") (pin "P$6") (pinfunction "DRAIN_P$6") (pintype "bidirectional"))
      (node (ref "Q1") (pin "P$7") (pinfunction "DRAIN_P$7") (pintype "bidirectional"))
      (node (ref "Q1") (pin "P$8") (pinfunction "DRAIN_P$8") (pintype "bidirectional"))
      (node (ref "Q1") (pin "P$9") (pinfunction "DRAIN_P$9") (pintype "bidirectional"))
      (node (ref "R3") (pin "P$1") (pinfunction "P$1_P$1") (pintype "passive"))
    )
    (net (code "53") (name "Net-(CON2-PadP$2)") (class "Default")
      (node (ref "CON2") (pin "P$2") (pinfunction "P$2_P$2") (pintype "bidirectional"))
      (node (ref "D2") (pin "ANODE") (pinfunction "ANODE_ANODE") (pintype "bidirectional"))
      (node (ref "Q2") (pin "P$5") (pinfunction "DRAIN_P$5") (pintype "bidirectional"))
      (node (ref "Q2") (pin "P$6") (pinfunction "DRAIN_P$6") (pintype "bidirectional"))
      (node (ref "Q2") (pin "P$7") (pinfunction "DRAIN_P$7") (pintype "bidirectional"))
      (node (ref "Q2") (pin "P$8") (pinfunction "DRAIN_P$8") (pintype "bidirectional"))
      (node (ref "Q2") (pin "P$9") (pinfunction "DRAIN_P$9") (pintype "bidirectional"))
      (node (ref "R4") (pin "P$1") (pinfunction "P$1_P$1") (pintype "passive"))
    )
    (net (code "54") (name "Net-(CON3-PadP$2)") (class "Default")
      (node (ref "CON3") (pin "P$2") (pinfunction "P$2_P$2") (pintype "bidirectional"))
      (node (ref "D3") (pin "ANODE") (pinfunction "ANODE_ANODE") (pintype "bidirectional"))
      (node (ref "Q3") (pin "P$5") (pinfunction "DRAIN_P$5") (pintype "bidirectional"))
      (node (ref "Q3") (pin "P$6") (pinfunction "DRAIN_P$6") (pintype "bidirectional"))
      (node (ref "Q3") (pin "P$7") (pinfunction "DRAIN_P$7") (pintype "bidirectional"))
      (node (ref "Q3") (pin "P$8") (pinfunction "DRAIN_P$8") (pintype "bidirectional"))
      (node (ref "Q3") (pin "P$9") (pinfunction "DRAIN_P$9") (pintype "bidirectional"))
      (node (ref "R5") (pin "P$1") (pinfunction "P$1_P$1") (pintype "passive"))
    )
    (net (code "55") (name "Net-(CON4-PadP$2)") (class "Default")
      (node (ref "CON4") (pin "P$2") (pinfunction "P$2_P$2") (pintype "bidirectional"))
      (node (ref "D4") (pin "ANODE") (pinfunction "ANODE_ANODE") (pintype "bidirectional"))
      (node (ref "Q4") (pin "P$5") (pinfunction "DRAIN_P$5") (pintype "bidirectional"))
      (node (ref "Q4") (pin "P$6") (pinfunction "DRAIN_P$6") (pintype "bidirectional"))
      (node (ref "Q4") (pin "P$7") (pinfunction "DRAIN_P$7") (pintype "bidirectional"))
      (node (ref "Q4") (pin "P$8") (pinfunction "DRAIN_P$8") (pintype "bidirectional"))
      (node (ref "Q4") (pin "P$9") (pinfunction "DRAIN_P$9") (pintype "bidirectional"))
      (node (ref "R6") (pin "P$1") (pinfunction "P$1_P$1") (pintype "passive"))
    )
    (net (code "56") (name "Net-(CON5-PadP$2)") (class "Default")
      (node (ref "CON5") (pin "P$2") (pinfunction "P$2_P$2") (pintype "bidirectional"))
      (node (ref "D5") (pin "ANODE") (pinfunction "ANODE_ANODE") (pintype "bidirectional"))
      (node (ref "Q5") (pin "P$5") (pinfunction "DRAIN_P$5") (pintype "bidirectional"))
      (node (ref "Q5") (pin "P$6") (pinfunction "DRAIN_P$6") (pintype "bidirectional"))
      (node (ref "Q5") (pin "P$7") (pinfunction "DRAIN_P$7") (pintype "bidirectional"))
      (node (ref "Q5") (pin "P$8") (pinfunction "DRAIN_P$8") (pintype "bidirectional"))
      (node (ref "Q5") (pin "P$9") (pinfunction "DRAIN_P$9") (pintype "bidirectional"))
      (node (ref "R21") (pin "P$1") (pinfunction "P$1_P$1") (pintype "passive"))
    )
    (net (code "57") (name "Net-(CON6-PadP$2)") (class "Default")
      (node (ref "CON6") (pin "P$2") (pinfunction "P$2_P$2") (pintype "bidirectional"))
      (node (ref "D6") (pin "ANODE") (pinfunction "ANODE_ANODE") (pintype "bidirectional"))
      (node (ref "Q6") (pin "P$5") (pinfunction "DRAIN_P$5") (pintype "bidirectional"))
      (node (ref "Q6") (pin "P$6") (pinfunction "DRAIN_P$6") (pintype "bidirectional"))
      (node (ref "Q6") (pin "P$7") (pinfunction "DRAIN_P$7") (pintype "bidirectional"))
      (node (ref "Q6") (pin "P$8") (pinfunction "DRAIN_P$8") (pintype "bidirectional"))
      (node (ref "Q6") (pin "P$9") (pinfunction "DRAIN_P$9") (pintype "bidirectional"))
      (node (ref "R22") (pin "P$1") (pinfunction "P$1_P$1") (pintype "passive"))
    )
    (net (code "58") (name "Net-(CON7-PadP$2)") (class "Default")
      (node (ref "CON7") (pin "P$2") (pinfunction "P$2_P$2") (pintype "bidirectional"))
      (node (ref "D7") (pin "ANODE") (pinfunction "ANODE_ANODE") (pintype "bidirectional"))
      (node (ref "Q7") (pin "P$5") (pinfunction "DRAIN_P$5") (pintype "bidirectional"))
      (node (ref "Q7") (pin "P$6") (pinfunction "DRAIN_P$6") (pintype "bidirectional"))
      (node (ref "Q7") (pin "P$7") (pinfunction "DRAIN_P$7") (pintype "bidirectional"))
      (node (ref "Q7") (pin "P$8") (pinfunction "DRAIN_P$8") (pintype "bidirectional"))
      (node (ref "Q7") (pin "P$9") (pinfunction "DRAIN_P$9") (pintype "bidirectional"))
      (node (ref "R23") (pin "P$1") (pinfunction "P$1_P$1") (pintype "passive"))
    )
    (net (code "59") (name "Net-(CON8-PadP$2)") (class "Default")
      (node (ref "CON8") (pin "P$2") (pinfunction "P$2_P$2") (pintype "bidirectional"))
      (node (ref "D8") (pin "ANODE") (pinfunction "ANODE_ANODE") (pintype "bidirectional"))
      (node (ref "Q8") (pin "P$5") (pinfunction "DRAIN_P$5") (pintype "bidirectional"))
      (node (ref "Q8") (pin "P$6") (pinfunction "DRAIN_P$6") (pintype "bidirectional"))
      (node (ref "Q8") (pin "P$7") (pinfunction "DRAIN_P$7") (pintype "bidirectional"))
      (node (ref "Q8") (pin "P$8") (pinfunction "DRAIN_P$8") (pintype "bidirectional"))
      (node (ref "Q8") (pin "P$9") (pinfunction "DRAIN_P$9") (pintype "bidirectional"))
      (node (ref "R24") (pin "P$1") (pinfunction "P$1_P$1") (pintype "passive"))
    )
    (net (code "60") (name "Net-(CON15-PadP$1)") (class "Default")
      (node (ref "CON15") (pin "P$1") (pinfunction "P$1_P$1") (pintype "bidirectional"))
      (node (ref "R106") (pin "P$2") (pinfunction "P$2_P$2") (pintype "passive"))
    )
    (net (code "61") (name "Net-(CON15-PadP$2)") (class "Default")
      (node (ref "CON15") (pin "P$2") (pinfunction "P$2_P$2") (pintype "bidirectional"))
      (node (ref "R107") (pin "P$2") (pinfunction "P$2_P$2") (pintype "passive"))
    )
    (net (code "62") (name "Net-(CON15-PadP$3)") (class "Default")
      (node (ref "CON15") (pin "P$3") (pinfunction "P$3_P$3") (pintype "bidirectional"))
      (node (ref "R108") (pin "P$2") (pinfunction "P$2_P$2") (pintype "passive"))
    )
    (net (code "63") (name "Net-(CON15-PadP$4)") (class "Default")
      (node (ref "CON15") (pin "P$4") (pinfunction "P$4_P$4") (pintype "bidirectional"))
      (node (ref "R109") (pin "P$2") (pinfunction "P$2_P$2") (pintype "passive"))
    )
    (net (code "64") (name "Net-(CON15-PadP$5)") (class "Default")
      (node (ref "CON15") (pin "P$5") (pinfunction "P$5_P$5") (pintype "bidirectional"))
      (node (ref "R110") (pin "P$2") (pinfunction "P$2_P$2") (pintype "passive"))
    )
    (net (code "65") (name "Net-(D9-PadCATHODE)") (class "Default")
      (node (ref "D9") (pin "CATHODE") (pinfunction "CATHODE_CATHODE") (pintype "bidirectional"))
      (node (ref "R60") (pin "P$1") (pinfunction "P$1_P$1") (pintype "passive"))
    )
    (net (code "66") (name "Net-(D10-PadCATHODE)") (class "Default")
      (node (ref "D10") (pin "CATHODE") (pinfunction "CATHODE_CATHODE") (pintype "bidirectional"))
      (node (ref "R42") (pin "P$1") (pinfunction "P$1_P$1") (pintype "passive"))
    )
    (net (code "67") (name "Net-(D11-PadCATHODE)") (class "Default")
      (node (ref "D11") (pin "CATHODE") (pinfunction "CATHODE_CATHODE") (pintype "bidirectional"))
      (node (ref "R43") (pin "P$1") (pinfunction "P$1_P$1") (pintype "passive"))
    )
    (net (code "68") (name "Net-(D12-PadCATHODE)") (class "Default")
      (node (ref "D12") (pin "CATHODE") (pinfunction "CATHODE_CATHODE") (pintype "bidirectional"))
      (node (ref "R44") (pin "P$1") (pinfunction "P$1_P$1") (pintype "passive"))
    )
    (net (code "69") (name "Net-(D13-PadCATHODE)") (class "Default")
      (node (ref "D13") (pin "CATHODE") (pinfunction "CATHODE_CATHODE") (pintype "bidirectional"))
      (node (ref "R92") (pin "P$1") (pinfunction "P$1_P$1") (pintype "passive"))
    )
    (net (code "70") (name "Net-(D14-PadCATHODE)") (class "Default")
      (node (ref "D14") (pin "CATHODE") (pinfunction "CATHODE_CATHODE") (pintype "bidirectional"))
      (node (ref "R74") (pin "P$1") (pinfunction "P$1_P$1") (pintype "passive"))
    )
    (net (code "71") (name "Net-(D15-PadCATHODE)") (class "Default")
      (node (ref "D15") (pin "CATHODE") (pinfunction "CATHODE_CATHODE") (pintype "bidirectional"))
      (node (ref "R75") (pin "P$1") (pinfunction "P$1_P$1") (pintype "passive"))
    )
    (net (code "72") (name "Net-(D16-PadCATHODE)") (class "Default")
      (node (ref "D16") (pin "CATHODE") (pinfunction "CATHODE_CATHODE") (pintype "bidirectional"))
      (node (ref "R76") (pin "P$1") (pinfunction "P$1_P$1") (pintype "passive"))
    )
    (net (code "73") (name "Net-(D17-PadANODE)") (class "Default")
      (node (ref "D17") (pin "ANODE") (pinfunction "ANODE_ANODE") (pintype "power_in"))
      (node (ref "R103") (pin "P$1") (pinfunction "P$1_P$1") (pintype "passive"))
    )
    (net (code "74") (name "Net-(D18-PadANODE)") (class "Default")
      (node (ref "D18") (pin "ANODE") (pinfunction "ANODE_ANODE") (pintype "power_in"))
      (node (ref "R97") (pin "P$1") (pinfunction "P$1_P$1") (pintype "passive"))
    )
    (net (code "75") (name "Net-(D19-PadANODE)") (class "Default")
      (node (ref "D19") (pin "ANODE") (pinfunction "ANODE_ANODE") (pintype "power_in"))
      (node (ref "R98") (pin "P$1") (pinfunction "P$1_P$1") (pintype "passive"))
    )
    (net (code "76") (name "Net-(D20-PadANODE)") (class "Default")
      (node (ref "D20") (pin "ANODE") (pinfunction "ANODE_ANODE") (pintype "power_in"))
      (node (ref "R99") (pin "P$1") (pinfunction "P$1_P$1") (pintype "passive"))
    )
    (net (code "77") (name "Net-(D21-PadANODE)") (class "Default")
      (node (ref "D21") (pin "ANODE") (pinfunction "ANODE_ANODE") (pintype "power_in"))
      (node (ref "R100") (pin "P$1") (pinfunction "P$1_P$1") (pintype "passive"))
    )
    (net (code "78") (name "Net-(F3-P$1-PadP$2)") (class "Default")
      (node (ref "F3") (pin "P$1") (pinfunction "P$1_P$1") (pintype "bidirectional"))
      (node (ref "F3") (pin "P$2") (pinfunction "P$1_P$2") (pintype "bidirectional"))
      (node (ref "F3") (pin "P$3") (pinfunction "P$1_P$3") (pintype "bidirectional"))
      (node (ref "F3") (pin "P$4") (pinfunction "P$1_P$4") (pintype "bidirectional"))
      (node (ref "RELAY3") (pin "30") (pinfunction "30_30") (pintype "bidirectional"))
    )
    (net (code "79") (name "Net-(JP2-Pad2)") (class "Default")
      (node (ref "JP2") (pin "2") (pinfunction "2_2") (pintype "passive"))
      (node (ref "R102") (pin "P$2") (pinfunction "P$2_P$2") (pintype "passive"))
    )
    (net (code "80") (name "Net-(Q9-DRAIN)") (class "Default")
      (node (ref "Q9") (pin "P$3") (pinfunction "DRAIN_P$3") (pintype "bidirectional"))
      (node (ref "RELAY3") (pin "85") (pinfunction "85_85") (pintype "bidirectional"))
    )
    (net (code "81") (name "Net-(Q10-D)") (class "Default")
      (node (ref "D17") (pin "CATHODE") (pinfunction "CATHODE_CATHODE") (pintype "power_in"))
      (node (ref "Q10") (pin "P$3") (pinfunction "D_P$3") (pintype "passive"))
      (node (ref "RELAY1") (pin "P$12") (pinfunction "P$12_P$12") (pintype "bidirectional"))
    )
    (net (code "82") (name "Net-(U5-IN+)") (class "Default")
      (node (ref "R61") (pin "P$2") (pinfunction "P$2_P$2") (pintype "passive"))
      (node (ref "R64") (pin "P$2") (pinfunction "P$2_P$2") (pintype "passive"))
      (node (ref "U5") (pin "P$3") (pinfunction "IN+_P$3") (pintype "bidirectional"))
    )
    (net (code "83") (name "Net-(U5-IN-)") (class "Default")
      (node (ref "R62") (pin "P$2") (pinfunction "P$2_P$2") (pintype "passive"))
      (node (ref "R63") (pin "P$2") (pinfunction "P$2_P$2") (pintype "passive"))
      (node (ref "U5") (pin "P$4") (pinfunction "IN-_P$4") (pintype "bidirectional"))
    )
    (net (code "84") (name "Net-(U5-OUT)") (class "Default")
      (node (ref "D9") (pin "ANODE") (pinfunction "ANODE_ANODE") (pintype "bidirectional"))
      (node (ref "R62") (pin "P$1") (pinfunction "P$1_P$1") (pintype "passive"))
      (node (ref "U5") (pin "P$1") (pinfunction "OUT_P$1") (pintype "bidirectional"))
    )
    (net (code "85") (name "Net-(U6-IN+)") (class "Default")
      (node (ref "R45") (pin "P$2") (pinfunction "P$2_P$2") (pintype "passive"))
      (node (ref "R52") (pin "P$2") (pinfunction "P$2_P$2") (pintype "passive"))
      (node (ref "U6") (pin "P$3") (pinfunction "IN+_P$3") (pintype "bidirectional"))
    )
    (net (code "86") (name "Net-(U6-IN-)") (class "Default")
      (node (ref "R48") (pin "P$2") (pinfunction "P$2_P$2") (pintype "passive"))
      (node (ref "R51") (pin "P$2") (pinfunction "P$2_P$2") (pintype "passive"))
      (node (ref "U6") (pin "P$4") (pinfunction "IN-_P$4") (pintype "bidirectional"))
    )
    (net (code "87") (name "Net-(U6-OUT)") (class "Default")
      (node (ref "D10") (pin "ANODE") (pinfunction "ANODE_ANODE") (pintype "bidirectional"))
      (node (ref "R48") (pin "P$1") (pinfunction "P$1_P$1") (pintype "passive"))
      (node (ref "U6") (pin "P$1") (pinfunction "OUT_P$1") (pintype "bidirectional"))
    )
    (net (code "88") (name "Net-(U7-IN+)") (class "Default")
      (node (ref "R46") (pin "P$2") (pinfunction "P$2_P$2") (pintype "passive"))
      (node (ref "R54") (pin "P$2") (pinfunction "P$2_P$2") (pintype "passive"))
      (node (ref "U7") (pin "P$3") (pinfunction "IN+_P$3") (pintype "bidirectional"))
    )
    (net (code "89") (name "Net-(U7-IN-)") (class "Default")
      (node (ref "R49") (pin "P$2") (pinfunction "P$2_P$2") (pintype "passive"))
      (node (ref "R53") (pin "P$2") (pinfunction "P$2_P$2") (pintype "passive"))
      (node (ref "U7") (pin "P$4") (pinfunction "IN-_P$4") (pintype "bidirectional"))
    )
    (net (code "90") (name "Net-(U7-OUT)") (class "Default")
      (node (ref "D11") (pin "ANODE") (pinfunction "ANODE_ANODE") (pintype "bidirectional"))
      (node (ref "R49") (pin "P$1") (pinfunction "P$1_P$1") (pintype "passive"))
      (node (ref "U7") (pin "P$1") (pinfunction "OUT_P$1") (pintype "bidirectional"))
    )
    (net (code "91") (name "Net-(U8-IN+)") (class "Default")
      (node (ref "R47") (pin "P$2") (pinfunction "P$2_P$2") (pintype "passive"))
      (node (ref "R56") (pin "P$2") (pinfunction "P$2_P$2") (pintype "passive"))
      (node (ref "U8") (pin "P$3") (pinfunction "IN+_P$3") (pintype "bidirectional"))
    )
    (net (code "92") (name "Net-(U8-IN-)") (class "Default")
      (node (ref "R50") (pin "P$2") (pinfunction "P$2_P$2") (pintype "passive"))
      (node (ref "R55") (pin "P$2") (pinfunction "P$2_P$2") (pintype "passive"))
      (node (ref "U8") (pin "P$4") (pinfunction "IN-_P$4") (pintype "bidirectional"))
    )
    (net (code "93") (name "Net-(U8-OUT)") (class "Default")
      (node (ref "D12") (pin "ANODE") (pinfunction "ANODE_ANODE") (pintype "bidirectional"))
      (node (ref "R50") (pin "P$1") (pinfunction "P$1_P$1") (pintype "passive"))
      (node (ref "U8") (pin "P$1") (pinfunction "OUT_P$1") (pintype "bidirectional"))
    )
    (net (code "94") (name "Net-(U9-IN+)") (class "Default")
      (node (ref "R93") (pin "P$2") (pinfunction "P$2_P$2") (pintype "passive"))
      (node (ref "R96") (pin "P$2") (pinfunction "P$2_P$2") (pintype "passive"))
      (node (ref "U9") (pin "P$3") (pinfunction "IN+_P$3") (pintype "bidirectional"))
    )
    (net (code "95") (name "Net-(U9-IN-)") (class "Default")
      (node (ref "R94") (pin "P$2") (pinfunction "P$2_P$2") (pintype "passive"))
      (node (ref "R95") (pin "P$2") (pinfunction "P$2_P$2") (pintype "passive"))
      (node (ref "U9") (pin "P$4") (pinfunction "IN-_P$4") (pintype "bidirectional"))
    )
    (net (code "96") (name "Net-(U9-OUT)") (class "Default")
      (node (ref "D13") (pin "ANODE") (pinfunction "ANODE_ANODE") (pintype "bidirectional"))
      (node (ref "R94") (pin "P$1") (pinfunction "P$1_P$1") (pintype "passive"))
      (node (ref "U9") (pin "P$1") (pinfunction "OUT_P$1") (pintype "bidirectional"))
    )
    (net (code "97") (name "Net-(U10-IN+)") (class "Default")
      (node (ref "R77") (pin "P$2") (pinfunction "P$2_P$2") (pintype "passive"))
      (node (ref "R84") (pin "P$2") (pinfunction "P$2_P$2") (pintype "passive"))
      (node (ref "U10") (pin "P$3") (pinfunction "IN+_P$3") (pintype "bidirectional"))
    )
    (net (code "98") (name "Net-(U10-IN-)") (class "Default")
      (node (ref "R80") (pin "P$2") (pinfunction "P$2_P$2") (pintype "passive"))
      (node (ref "R83") (pin "P$2") (pinfunction "P$2_P$2") (pintype "passive"))
      (node (ref "U10") (pin "P$4") (pinfunction "IN-_P$4") (pintype "bidirectional"))
    )
    (net (code "99") (name "Net-(U10-OUT)") (class "Default")
      (node (ref "D14") (pin "ANODE") (pinfunction "ANODE_ANODE") (pintype "bidirectional"))
      (node (ref "R80") (pin "P$1") (pinfunction "P$1_P$1") (pintype "passive"))
      (node (ref "U10") (pin "P$1") (pinfunction "OUT_P$1") (pintype "bidirectional"))
    )
    (net (code "100") (name "Net-(U11-IN+)") (class "Default")
      (node (ref "R78") (pin "P$2") (pinfunction "P$2_P$2") (pintype "passive"))
      (node (ref "R86") (pin "P$2") (pinfunction "P$2_P$2") (pintype "passive"))
      (node (ref "U11") (pin "P$3") (pinfunction "IN+_P$3") (pintype "bidirectional"))
    )
    (net (code "101") (name "Net-(U11-IN-)") (class "Default")
      (node (ref "R81") (pin "P$2") (pinfunction "P$2_P$2") (pintype "passive"))
      (node (ref "R85") (pin "P$2") (pinfunction "P$2_P$2") (pintype "passive"))
      (node (ref "U11") (pin "P$4") (pinfunction "IN-_P$4") (pintype "bidirectional"))
    )
    (net (code "102") (name "Net-(U11-OUT)") (class "Default")
      (node (ref "D15") (pin "ANODE") (pinfunction "ANODE_ANODE") (pintype "bidirectional"))
      (node (ref "R81") (pin "P$1") (pinfunction "P$1_P$1") (pintype "passive"))
      (node (ref "U11") (pin "P$1") (pinfunction "OUT_P$1") (pintype "bidirectional"))
    )
    (net (code "103") (name "Net-(U12-IN+)") (class "Default")
      (node (ref "R79") (pin "P$2") (pinfunction "P$2_P$2") (pintype "passive"))
      (node (ref "R88") (pin "P$2") (pinfunction "P$2_P$2") (pintype "passive"))
      (node (ref "U12") (pin "P$3") (pinfunction "IN+_P$3") (pintype "bidirectional"))
    )
    (net (code "104") (name "Net-(U12-IN-)") (class "Default")
      (node (ref "R82") (pin "P$2") (pinfunction "P$2_P$2") (pintype "passive"))
      (node (ref "R87") (pin "P$2") (pinfunction "P$2_P$2") (pintype "passive"))
      (node (ref "U12") (pin "P$4") (pinfunction "IN-_P$4") (pintype "bidirectional"))
    )
    (net (code "105") (name "Net-(U12-OUT)") (class "Default")
      (node (ref "D16") (pin "ANODE") (pinfunction "ANODE_ANODE") (pintype "bidirectional"))
      (node (ref "R82") (pin "P$1") (pinfunction "P$1_P$1") (pintype "passive"))
      (node (ref "U12") (pin "P$1") (pinfunction "OUT_P$1") (pintype "bidirectional"))
    )
    (net (code "106") (name "Net-(U14-RS)") (class "Default")
      (node (ref "R105") (pin "P$1") (pinfunction "P$1_P$1") (pintype "passive"))
      (node (ref "U14") (pin "8") (pinfunction "RS_8") (pintype "bidirectional"))
    )
    (net (code "107") (name "Net-(U15-OSC1)") (class "Default")
      (node (ref "C53") (pin "P$2") (pinfunction "P$2_P$2") (pintype "passive"))
      (node (ref "U15") (pin "8") (pinfunction "OSC1_8") (pintype "input"))
      (node (ref "X1") (pin "1") (pinfunction "1_1") (pintype "passive"))
    )
    (net (code "108") (name "Net-(U15-OSC2)") (class "Default")
      (node (ref "C52") (pin "P$2") (pinfunction "P$2_P$2") (pintype "passive"))
      (node (ref "U15") (pin "7") (pinfunction "OSC2_7") (pintype "output"))
      (node (ref "X1") (pin "2") (pinfunction "2_2") (pintype "passive"))
    )
    (net (code "109") (name "Net-(U15-~{RESET})") (class "Default")
      (node (ref "R104") (pin "P$2") (pinfunction "P$2_P$2") (pintype "passive"))
      (node (ref "U15") (pin "17") (pinfunction "~{RESET}_17") (pintype "input"))
    )
    (net (code "110") (name "PA0") (class "Default")
      (node (ref "XIO") (pin "3") (pinfunction "3_3") (pintype "passive"))
    )
    (net (code "111") (name "PA1") (class "Default")
      (node (ref "XIO") (pin "4") (pinfunction "4_4") (pintype "passive"))
    )
    (net (code "112") (name "PA2") (class "Default")
      (node (ref "XIO") (pin "5") (pinfunction "5_5") (pintype "passive"))
    )
    (net (code "113") (name "PA3") (class "Default")
      (node (ref "XIO") (pin "6") (pinfunction "6_6") (pintype "passive"))
    )
    (net (code "114") (name "PA4") (class "Default")
      (node (ref "XIO") (pin "7") (pinfunction "7_7") (pintype "passive"))
    )
    (net (code "115") (name "PA5") (class "Default")
      (node (ref "XIO") (pin "8") (pinfunction "8_8") (pintype "passive"))
    )
    (net (code "116") (name "PA6") (class "Default")
      (node (ref "XIO") (pin "9") (pinfunction "9_9") (pintype "passive"))
    )
    (net (code "117") (name "PA7") (class "Default")
      (node (ref "XIO") (pin "10") (pinfunction "10_10") (pintype "passive"))
    )
    (net (code "118") (name "PB4") (class "Default")
      (node (ref "JP1") (pin "8") (pinfunction "8_8") (pintype "passive"))
    )
    (net (code "119") (name "PB5") (class "Default")
      (node (ref "JP1") (pin "7") (pinfunction "7_7") (pintype "passive"))
    )
    (net (code "120") (name "PB6") (class "Default")
      (node (ref "JP1") (pin "6") (pinfunction "6_6") (pintype "passive"))
    )
    (net (code "121") (name "PB7") (class "Default")
      (node (ref "JP1") (pin "5") (pinfunction "5_5") (pintype "passive"))
    )
    (net (code "122") (name "PC0") (class "Default")
      (node (ref "XIO") (pin "18") (pinfunction "18_18") (pintype "passive"))
    )
    (net (code "123") (name "PC1") (class "Default")
      (node (ref "XIO") (pin "17") (pinfunction "17_17") (pintype "passive"))
    )
    (net (code "124") (name "PC2") (class "Default")
      (node (ref "XIO") (pin "16") (pinfunction "16_16") (pintype "passive"))
    )
    (net (code "125") (name "PC3") (class "Default")
      (node (ref "XIO") (pin "15") (pinfunction "15_15") (pintype "passive"))
    )
    (net (code "126") (name "PC4") (class "Default")
      (node (ref "XIO") (pin "14") (pinfunction "14_14") (pintype "passive"))
    )
    (net (code "127") (name "PC5") (class "Default")
      (node (ref "XIO") (pin "13") (pinfunction "13_13") (pintype "passive"))
    )
    (net (code "128") (name "PC6") (class "Default")
      (node (ref "XIO") (pin "12") (pinfunction "12_12") (pintype "passive"))
    )
    (net (code "129") (name "PC7") (class "Default")
      (node (ref "XIO") (pin "11") (pinfunction "11_11") (pintype "passive"))
    )
    (net (code "130") (name "PD7") (class "Default")
      (node (ref "XIO") (pin "19") (pinfunction "19_19") (pintype "passive"))
    )
    (net (code "131") (name "PG0") (class "Default")
      (node (ref "XIO") (pin "22") (pinfunction "22_22") (pintype "passive"))
    )
    (net (code "132") (name "PG1") (class "Default")
      (node (ref "XIO") (pin "21") (pinfunction "21_21") (pintype "passive"))
    )
    (net (code "133") (name "PG2") (class "Default")
      (node (ref "XIO") (pin "20") (pinfunction "20_20") (pintype "passive"))
    )
    (net (code "134") (name "PH6") (class "Default")
      (node (ref "JP1") (pin "9") (pinfunction "9_9") (pintype "passive"))
    )
    (net (code "135") (name "PL2") (class "Default")
      (node (ref "XIO") (pin "28") (pinfunction "28_28") (pintype "passive"))
    )
    (net (code "136") (name "PL3") (class "Default")
      (node (ref "XIO") (pin "27") (pinfunction "27_27") (pintype "passive"))
    )
    (net (code "137") (name "PL6") (class "Default")
      (node (ref "XIO") (pin "24") (pinfunction "24_24") (pintype "passive"))
    )
    (net (code "138") (name "PL7") (class "Default")
      (node (ref "XIO") (pin "23") (pinfunction "23_23") (pintype "passive"))
    )
    (net (code "139") (name "PUMP_EN") (class "Default")
      (node (ref "Q9") (pin "P$1") (pinfunction "GATE_P$1") (pintype "bidirectional"))
      (node (ref "XIO") (pin "30") (pinfunction "30_30") (pintype "passive"))
    )
    (net (code "140") (name "PUMP_POWER") (class "Default")
      (node (ref "CON11") (pin "P$1") (pinfunction "P$1_P$1") (pintype "bidirectional"))
      (node (ref "CON11") (pin "P$2") (pinfunction "P$1_P$2") (pintype "bidirectional"))
      (node (ref "RELAY3") (pin "87") (pinfunction "87_87") (pintype "bidirectional"))
    )
    (net (code "141") (name "RELAY_COM_A") (class "Default")
      (node (ref "CON9") (pin "P$2") (pinfunction "P$2_P$2") (pintype "bidirectional"))
      (node (ref "RELAY1") (pin "P$4") (pinfunction "P$4_P$4") (pintype "bidirectional"))
    )
    (net (code "142") (name "RELAY_COM_B") (class "Default")
      (node (ref "CON10") (pin "P$2") (pinfunction "P$2_P$2") (pintype "bidirectional"))
      (node (ref "RELAY1") (pin "P$9") (pinfunction "P$9_P$9") (pintype "bidirectional"))
    )
    (net (code "143") (name "RELAY_EN") (class "Default")
      (node (ref "Q10") (pin "P$1") (pinfunction "G_P$1") (pintype "passive"))
      (node (ref "XIO") (pin "29") (pinfunction "29_29") (pintype "passive"))
    )
    (net (code "144") (name "RELAY_NC_A") (class "Default")
      (node (ref "CON9") (pin "P$1") (pinfunction "P$1_P$1") (pintype "bidirectional"))
      (node (ref "RELAY1") (pin "P$3") (pinfunction "P$3_P$3") (pintype "bidirectional"))
    )
    (net (code "145") (name "RELAY_NC_B") (class "Default")
      (node (ref "CON10") (pin "P$3") (pinfunction "P$3_P$3") (pintype "bidirectional"))
      (node (ref "RELAY1") (pin "P$10") (pinfunction "P$10_P$10") (pintype "bidirectional"))
    )
    (net (code "146") (name "RELAY_NO_A") (class "Default")
      (node (ref "CON9") (pin "P$3") (pinfunction "P$3_P$3") (pintype "bidirectional"))
      (node (ref "RELAY1") (pin "P$5") (pinfunction "P$5_P$5") (pintype "bidirectional"))
    )
    (net (code "147") (name "RELAY_NO_B") (class "Default")
      (node (ref "CON10") (pin "P$1") (pinfunction "P$1_P$1") (pintype "bidirectional"))
      (node (ref "RELAY1") (pin "P$8") (pinfunction "P$8_P$8") (pintype "bidirectional"))
    )
    (net (code "148") (name "RESET") (class "Default")
      (node (ref "POWER") (pin "3") (pinfunction "3_3") (pintype "passive"))
    )
    (net (code "149") (name "RXD1") (class "Default")
      (node (ref "COMMUNICATION") (pin "3") (pinfunction "3_3") (pintype "passive"))
    )
    (net (code "150") (name "RXD2") (class "Default")
      (node (ref "COMMUNICATION") (pin "5") (pinfunction "5_5") (pintype "passive"))
    )
    (net (code "151") (name "RXD3") (class "Default")
      (node (ref "COMMUNICATION") (pin "7") (pinfunction "7_7") (pintype "passive"))
    )
    (net (code "152") (name "RX_CAN") (class "Default")
      (node (ref "D20") (pin "CATHODE") (pinfunction "CATHODE_CATHODE") (pintype "power_in"))
      (node (ref "U14") (pin "4") (pinfunction "RXD_4") (pintype "bidirectional"))
      (node (ref "U15") (pin "2") (pinfunction "RXCAN_2") (pintype "input"))
    )
    (net (code "153") (name "S1_G") (class "Default")
      (node (ref "Q3") (pin "P$4") (pinfunction "GATE_P$4") (pintype "bidirectional"))
      (node (ref "R1") (pin "P$1") (pinfunction "P$1_P$1") (pintype "passive"))
      (node (ref "U1") (pin "5") (pinfunction "OUTB_5") (pintype "bidirectional"))
    )
    (net (code "154") (name "S1_PWM") (class "Default")
      (node (ref "PWML") (pin "6") (pinfunction "6_6") (pintype "passive"))
      (node (ref "U1") (pin "4") (pinfunction "INB_4") (pintype "bidirectional"))
    )
    (net (code "155") (name "S1_SENS_N") (class "Default")
      (node (ref "R11") (pin "P$2") (pinfunction "P$2_P$2") (pintype "passive"))
      (node (ref "R15") (pin "P$2") (pinfunction "P$2_P$2") (pintype "passive"))
      (node (ref "R36") (pin "P$1") (pinfunction "P$1_P$1") (pintype "passive"))
    )
    (net (code "156") (name "S1_SENS_OUT") (class "Default")
      (node (ref "ADCL") (pin "1") (pinfunction "1_1") (pintype "passive"))
      (node (ref "C27") (pin "P$1") (pinfunction "P$1_P$1") (pintype "passive"))
      (node (ref "R33") (pin "P$2") (pinfunction "P$2_P$2") (pintype "passive"))
      (node (ref "R42") (pin "P$2") (pinfunction "P$2_P$2") (pintype "passive"))
    )
    (net (code "157") (name "S1_SENS_P") (class "Default")
      (node (ref "C7") (pin "P$2") (pinfunction "P$2_P$2") (pintype "passive"))
      (node (ref "Q3") (pin "P$1") (pinfunction "SOURCE_P$1") (pintype "bidirectional"))
      (node (ref "Q3") (pin "P$2") (pinfunction "SOURCE_P$2") (pintype "bidirectional"))
      (node (ref "Q3") (pin "P$3") (pinfunction "SOURCE_P$3") (pintype "bidirectional"))
      (node (ref "R11") (pin "P$1") (pinfunction "P$1_P$1") (pintype "passive"))
      (node (ref "R37") (pin "P$1") (pinfunction "P$1_P$1") (pintype "passive"))
    )
    (net (code "158") (name "S2_G") (class "Default")
      (node (ref "Q4") (pin "P$4") (pinfunction "GATE_P$4") (pintype "bidirectional"))
      (node (ref "R2") (pin "P$1") (pinfunction "P$1_P$1") (pintype "passive"))
      (node (ref "U1") (pin "7") (pinfunction "OUTA_7") (pintype "bidirectional"))
    )
    (net (code "159") (name "S2_PWM") (class "Default")
      (node (ref "PWML") (pin "7") (pinfunction "7_7") (pintype "passive"))
      (node (ref "U1") (pin "2") (pinfunction "INA_2") (pintype "bidirectional"))
    )
    (net (code "160") (name "S2_SENS_N") (class "Default")
      (node (ref "R12") (pin "P$2") (pinfunction "P$2_P$2") (pintype "passive"))
      (node (ref "R16") (pin "P$2") (pinfunction "P$2_P$2") (pintype "passive"))
      (node (ref "R38") (pin "P$1") (pinfunction "P$1_P$1") (pintype "passive"))
    )
    (net (code "161") (name "S2_SENS_OUT") (class "Default")
      (node (ref "ADCL") (pin "2") (pinfunction "2_2") (pintype "passive"))
      (node (ref "C30") (pin "P$1") (pinfunction "P$1_P$1") (pintype "passive"))
      (node (ref "R34") (pin "P$2") (pinfunction "P$2_P$2") (pintype "passive"))
      (node (ref "R43") (pin "P$2") (pinfunction "P$2_P$2") (pintype "passive"))
    )
    (net (code "162") (name "S2_SENS_P") (class "Default")
      (node (ref "C8") (pin "P$2") (pinfunction "P$2_P$2") (pintype "passive"))
      (node (ref "Q4") (pin "P$1") (pinfunction "SOURCE_P$1") (pintype "bidirectional"))
      (node (ref "Q4") (pin "P$2") (pinfunction "SOURCE_P$2") (pintype "bidirectional"))
      (node (ref "Q4") (pin "P$3") (pinfunction "SOURCE_P$3") (pintype "bidirectional"))
      (node (ref "R12") (pin "P$1") (pinfunction "P$1_P$1") (pintype "passive"))
      (node (ref "R39") (pin "P$1") (pinfunction "P$1_P$1") (pintype "passive"))
    )
    (net (code "163") (name "S3_G") (class "Default")
      (node (ref "Q1") (pin "P$4") (pinfunction "GATE_P$4") (pintype "bidirectional"))
      (node (ref "R13") (pin "P$1") (pinfunction "P$1_P$1") (pintype "passive"))
      (node (ref "U2") (pin "5") (pinfunction "OUTB_5") (pintype "bidirectional"))
    )
    (net (code "164") (name "S3_PWM") (class "Default")
      (node (ref "PWML") (pin "3") (pinfunction "3_3") (pintype "passive"))
      (node (ref "U2") (pin "4") (pinfunction "INB_4") (pintype "bidirectional"))
    )
    (net (code "165") (name "S3_SENS_N") (class "Default")
      (node (ref "R40") (pin "P$1") (pinfunction "P$1_P$1") (pintype "passive"))
      (node (ref "R7") (pin "P$2") (pinfunction "P$2_P$2") (pintype "passive"))
      (node (ref "R9") (pin "P$2") (pinfunction "P$2_P$2") (pintype "passive"))
    )
    (net (code "166") (name "S3_SENS_OUT") (class "Default")
      (node (ref "ADCL") (pin "3") (pinfunction "3_3") (pintype "passive"))
      (node (ref "C33") (pin "P$1") (pinfunction "P$1_P$1") (pintype "passive"))
      (node (ref "R35") (pin "P$2") (pinfunction "P$2_P$2") (pintype "passive"))
      (node (ref "R44") (pin "P$2") (pinfunction "P$2_P$2") (pintype "passive"))
    )
    (net (code "167") (name "S3_SENS_P") (class "Default")
      (node (ref "C3") (pin "P$2") (pinfunction "P$2_P$2") (pintype "passive"))
      (node (ref "Q1") (pin "P$1") (pinfunction "SOURCE_P$1") (pintype "bidirectional"))
      (node (ref "Q1") (pin "P$2") (pinfunction "SOURCE_P$2") (pintype "bidirectional"))
      (node (ref "Q1") (pin "P$3") (pinfunction "SOURCE_P$3") (pintype "bidirectional"))
      (node (ref "R41") (pin "P$1") (pinfunction "P$1_P$1") (pintype "passive"))
      (node (ref "R7") (pin "P$1") (pinfunction "P$1_P$1") (pintype "passive"))
    )
    (net (code "168") (name "S4_G") (class "Default")
      (node (ref "Q2") (pin "P$4") (pinfunction "GATE_P$4") (pintype "bidirectional"))
      (node (ref "R14") (pin "P$1") (pinfunction "P$1_P$1") (pintype "passive"))
      (node (ref "U2") (pin "7") (pinfunction "OUTA_7") (pintype "bidirectional"))
    )
    (net (code "169") (name "S4_PWM") (class "Default")
      (node (ref "PWML") (pin "4") (pinfunction "4_4") (pintype "passive"))
      (node (ref "U2") (pin "2") (pinfunction "INA_2") (pintype "bidirectional"))
    )
    (net (code "170") (name "S4_SENS_N") (class "Default")
      (node (ref "R10") (pin "P$2") (pinfunction "P$2_P$2") (pintype "passive"))
      (node (ref "R58") (pin "P$1") (pinfunction "P$1_P$1") (pintype "passive"))
      (node (ref "R8") (pin "P$2") (pinfunction "P$2_P$2") (pintype "passive"))
    )
    (net (code "171") (name "S4_SENS_OUT") (class "Default")
      (node (ref "ADCL") (pin "4") (pinfunction "4_4") (pintype "passive"))
      (node (ref "C36") (pin "P$1") (pinfunction "P$1_P$1") (pintype "passive"))
      (node (ref "R57") (pin "P$2") (pinfunction "P$2_P$2") (pintype "passive"))
      (node (ref "R60") (pin "P$2") (pinfunction "P$2_P$2") (pintype "passive"))
    )
    (net (code "172") (name "S4_SENS_P") (class "Default")
      (node (ref "C4") (pin "P$2") (pinfunction "P$2_P$2") (pintype "passive"))
      (node (ref "Q2") (pin "P$1") (pinfunction "SOURCE_P$1") (pintype "bidirectional"))
      (node (ref "Q2") (pin "P$2") (pinfunction "SOURCE_P$2") (pintype "bidirectional"))
      (node (ref "Q2") (pin "P$3") (pinfunction "SOURCE_P$3") (pintype "bidirectional"))
      (node (ref "R59") (pin "P$1") (pinfunction "P$1_P$1") (pintype "passive"))
      (node (ref "R8") (pin "P$1") (pinfunction "P$1_P$1") (pintype "passive"))
    )
    (net (code "173") (name "S5_G") (class "Default")
      (node (ref "Q5") (pin "P$4") (pinfunction "GATE_P$4") (pintype "bidirectional"))
      (node (ref "R17") (pin "P$1") (pinfunction "P$1_P$1") (pintype "passive"))
      (node (ref "U3") (pin "7") (pinfunction "OUTA_7") (pintype "bidirectional"))
    )
    (net (code "174") (name "S5_PWM") (class "Default")
      (node (ref "PWML") (pin "8") (pinfunction "8_8") (pintype "passive"))
      (node (ref "U3") (pin "2") (pinfunction "INA_2") (pintype "bidirectional"))
    )
    (net (code "175") (name "S5_SENS_N") (class "Default")
      (node (ref "R25") (pin "P$2") (pinfunction "P$2_P$2") (pintype "passive"))
      (node (ref "R29") (pin "P$2") (pinfunction "P$2_P$2") (pintype "passive"))
      (node (ref "R68") (pin "P$1") (pinfunction "P$1_P$1") (pintype "passive"))
    )
    (net (code "176") (name "S5_SENS_OUT") (class "Default")
      (node (ref "ADCL") (pin "5") (pinfunction "5_5") (pintype "passive"))
      (node (ref "C39") (pin "P$1") (pinfunction "P$1_P$1") (pintype "passive"))
      (node (ref "R65") (pin "P$2") (pinfunction "P$2_P$2") (pintype "passive"))
      (node (ref "R74") (pin "P$2") (pinfunction "P$2_P$2") (pintype "passive"))
    )
    (net (code "177") (name "S5_SENS_P") (class "Default")
      (node (ref "C19") (pin "P$2") (pinfunction "P$2_P$2") (pintype "passive"))
      (node (ref "Q5") (pin "P$1") (pinfunction "SOURCE_P$1") (pintype "bidirectional"))
      (node (ref "Q5") (pin "P$2") (pinfunction "SOURCE_P$2") (pintype "bidirectional"))
      (node (ref "Q5") (pin "P$3") (pinfunction "SOURCE_P$3") (pintype "bidirectional"))
      (node (ref "R25") (pin "P$1") (pinfunction "P$1_P$1") (pintype "passive"))
      (node (ref "R69") (pin "P$1") (pinfunction "P$1_P$1") (pintype "passive"))
    )
    (net (code "178") (name "S6_G") (class "Default")
      (node (ref "Q6") (pin "P$4") (pinfunction "GATE_P$4") (pintype "bidirectional"))
      (node (ref "R18") (pin "P$1") (pinfunction "P$1_P$1") (pintype "passive"))
      (node (ref "U3") (pin "5") (pinfunction "OUTB_5") (pintype "bidirectional"))
    )
    (net (code "179") (name "S6_PWM") (class "Default")
      (node (ref "JP1") (pin "10") (pinfunction "10_10") (pintype "passive"))
      (node (ref "U3") (pin "4") (pinfunction "INB_4") (pintype "bidirectional"))
    )
    (net (code "180") (name "S6_SENS_N") (class "Default")
      (node (ref "R26") (pin "P$2") (pinfunction "P$2_P$2") (pintype "passive"))
      (node (ref "R30") (pin "P$2") (pinfunction "P$2_P$2") (pintype "passive"))
      (node (ref "R70") (pin "P$1") (pinfunction "P$1_P$1") (pintype "passive"))
    )
    (net (code "181") (name "S6_SENS_OUT") (class "Default")
      (node (ref "ADCL") (pin "6") (pinfunction "6_6") (pintype "passive"))
      (node (ref "C42") (pin "P$1") (pinfunction "P$1_P$1") (pintype "passive"))
      (node (ref "R66") (pin "P$2") (pinfunction "P$2_P$2") (pintype "passive"))
      (node (ref "R75") (pin "P$2") (pinfunction "P$2_P$2") (pintype "passive"))
    )
    (net (code "182") (name "S6_SENS_P") (class "Default")
      (node (ref "C20") (pin "P$2") (pinfunction "P$2_P$2") (pintype "passive"))
      (node (ref "Q6") (pin "P$1") (pinfunction "SOURCE_P$1") (pintype "bidirectional"))
      (node (ref "Q6") (pin "P$2") (pinfunction "SOURCE_P$2") (pintype "bidirectional"))
      (node (ref "Q6") (pin "P$3") (pinfunction "SOURCE_P$3") (pintype "bidirectional"))
      (node (ref "R26") (pin "P$1") (pinfunction "P$1_P$1") (pintype "passive"))
      (node (ref "R71") (pin "P$1") (pinfunction "P$1_P$1") (pintype "passive"))
    )
    (net (code "183") (name "S7_G") (class "Default")
      (node (ref "Q7") (pin "P$4") (pinfunction "GATE_P$4") (pintype "bidirectional"))
      (node (ref "R19") (pin "P$1") (pinfunction "P$1_P$1") (pintype "passive"))
      (node (ref "U4") (pin "7") (pinfunction "OUTA_7") (pintype "bidirectional"))
    )
    (net (code "184") (name "S7_PWM") (class "Default")
      (node (ref "U4") (pin "2") (pinfunction "INA_2") (pintype "bidirectional"))
      (node (ref "XIO") (pin "25") (pinfunction "25_25") (pintype "passive"))
    )
    (net (code "185") (name "S7_SENS_N") (class "Default")
      (node (ref "R27") (pin "P$2") (pinfunction "P$2_P$2") (pintype "passive"))
      (node (ref "R31") (pin "P$2") (pinfunction "P$2_P$2") (pintype "passive"))
      (node (ref "R72") (pin "P$1") (pinfunction "P$1_P$1") (pintype "passive"))
    )
    (net (code "186") (name "S7_SENS_OUT") (class "Default")
      (node (ref "ADCL") (pin "7") (pinfunction "7_7") (pintype "passive"))
      (node (ref "C45") (pin "P$1") (pinfunction "P$1_P$1") (pintype "passive"))
      (node (ref "R67") (pin "P$2") (pinfunction "P$2_P$2") (pintype "passive"))
      (node (ref "R76") (pin "P$2") (pinfunction "P$2_P$2") (pintype "passive"))
    )
    (net (code "187") (name "S7_SENS_P") (class "Default")
      (node (ref "C21") (pin "P$2") (pinfunction "P$2_P$2") (pintype "passive"))
      (node (ref "Q7") (pin "P$1") (pinfunction "SOURCE_P$1") (pintype "bidirectional"))
      (node (ref "Q7") (pin "P$2") (pinfunction "SOURCE_P$2") (pintype "bidirectional"))
      (node (ref "Q7") (pin "P$3") (pinfunction "SOURCE_P$3") (pintype "bidirectional"))
      (node (ref "R27") (pin "P$1") (pinfunction "P$1_P$1") (pintype "passive"))
      (node (ref "R73") (pin "P$1") (pinfunction "P$1_P$1") (pintype "passive"))
    )
    (net (code "188") (name "S8_G") (class "Default")
      (node (ref "Q8") (pin "P$4") (pinfunction "GATE_P$4") (pintype "bidirectional"))
      (node (ref "R20") (pin "P$1") (pinfunction "P$1_P$1") (pintype "passive"))
      (node (ref "U4") (pin "5") (pinfunction "OUTB_5") (pintype "bidirectional"))
    )
    (net (code "189") (name "S8_PWM") (class "Default")
      (node (ref "U4") (pin "4") (pinfunction "INB_4") (pintype "bidirectional"))
      (node (ref "XIO") (pin "26") (pinfunction "26_26") (pintype "passive"))
    )
    (net (code "190") (name "S8_SENS_N") (class "Default")
      (node (ref "R28") (pin "P$2") (pinfunction "P$2_P$2") (pintype "passive"))
      (node (ref "R32") (pin "P$2") (pinfunction "P$2_P$2") (pintype "passive"))
      (node (ref "R90") (pin "P$1") (pinfunction "P$1_P$1") (pintype "passive"))
    )
    (net (code "191") (name "S8_SENS_OUT") (class "Default")
      (node (ref "ADCL") (pin "8") (pinfunction "8_8") (pintype "passive"))
      (node (ref "C48") (pin "P$1") (pinfunction "P$1_P$1") (pintype "passive"))
      (node (ref "R89") (pin "P$2") (pinfunction "P$2_P$2") (pintype "passive"))
      (node (ref "R92") (pin "P$2") (pinfunction "P$2_P$2") (pintype "passive"))
    )
    (net (code "192") (name "S8_SENS_P") (class "Default")
      (node (ref "C22") (pin "P$2") (pinfunction "P$2_P$2") (pintype "passive"))
      (node (ref "Q8") (pin "P$1") (pinfunction "SOURCE_P$1") (pintype "bidirectional"))
      (node (ref "Q8") (pin "P$2") (pinfunction "SOURCE_P$2") (pintype "bidirectional"))
      (node (ref "Q8") (pin "P$3") (pinfunction "SOURCE_P$3") (pintype "bidirectional"))
      (node (ref "R28") (pin "P$1") (pinfunction "P$1_P$1") (pintype "passive"))
      (node (ref "R91") (pin "P$1") (pinfunction "P$1_P$1") (pintype "passive"))
    )
    (net (code "193") (name "SCK") (class "Default")
      (node (ref "U15") (pin "13") (pinfunction "SCK_13") (pintype "input"))
      (node (ref "XIO") (pin "33") (pinfunction "33_33") (pintype "passive"))
    )
    (net (code "194") (name "SCL") (class "Default")
      (node (ref "JP1") (pin "1") (pinfunction "1_1") (pintype "passive"))
    )
    (net (code "195") (name "SDA") (class "Default")
      (node (ref "JP1") (pin "2") (pinfunction "2_2") (pintype "passive"))
    )
    (net (code "196") (name "TXD1") (class "Default")
      (node (ref "COMMUNICATION") (pin "4") (pinfunction "4_4") (pintype "passive"))
    )
    (net (code "197") (name "TXD2") (class "Default")
      (node (ref "COMMUNICATION") (pin "6") (pinfunction "6_6") (pintype "passive"))
    )
    (net (code "198") (name "TXD3") (class "Default")
      (node (ref "COMMUNICATION") (pin "8") (pinfunction "8_8") (pintype "passive"))
    )
    (net (code "199") (name "TX_CAN") (class "Default")
      (node (ref "D19") (pin "CATHODE") (pinfunction "CATHODE_CATHODE") (pintype "power_in"))
      (node (ref "U14") (pin "1") (pinfunction "TXD_1") (pintype "bidirectional"))
      (node (ref "U15") (pin "1") (pinfunction "TXCAN_1") (pintype "output"))
    )
    (net (code "200") (name "V+") (class "Default")
      (node (ref "CON16") (pin "P$3") (pinfunction "P$2_P$3") (pintype "bidirectional"))
      (node (ref "CON16") (pin "P$4") (pinfunction "P$2_P$4") (pintype "bidirectional"))
      (node (ref "F1") (pin "P$1") (pinfunction "P$1_P$1") (pintype "bidirectional"))
      (node (ref "F1") (pin "P$2") (pinfunction "P$1_P$2") (pintype "bidirectional"))
      (node (ref "F1") (pin "P$3") (pinfunction "P$1_P$3") (pintype "bidirectional"))
      (node (ref "F1") (pin "P$4") (pinfunction "P$1_P$4") (pintype "bidirectional"))
      (node (ref "F2") (pin "P$1") (pinfunction "P$1_P$1") (pintype "bidirectional"))
      (node (ref "F2") (pin "P$2") (pinfunction "P$1_P$2") (pintype "bidirectional"))
      (node (ref "F2") (pin "P$3") (pinfunction "P$1_P$3") (pintype "bidirectional"))
      (node (ref "F2") (pin "P$4") (pinfunction "P$1_P$4") (pintype "bidirectional"))
      (node (ref "F3") (pin "P$5") (pinfunction "P$2_P$5") (pintype "bidirectional"))
      (node (ref "F3") (pin "P$6") (pinfunction "P$2_P$6") (pintype "bidirectional"))
      (node (ref "F3") (pin "P$7") (pinfunction "P$2_P$7") (pintype "bidirectional"))
      (node (ref "F3") (pin "P$8") (pinfunction "P$2_P$8") (pintype "bidirectional"))
      (node (ref "RELAY3") (pin "86") (pinfunction "86_86") (pintype "bidirectional"))
      (node (ref "U13") (pin "P$1") (pinfunction "VIN_P$1") (pintype "bidirectional"))
    )
    (net (code "201") (name "VB1") (class "Default")
      (node (ref "C11") (pin "P$1") (pinfunction "P$1_P$1") (pintype "passive"))
      (node (ref "C12") (pin "P$1") (pinfunction "P$1_P$1") (pintype "passive"))
      (node (ref "C5") (pin "P$1") (pinfunction "P$1_P$1") (pintype "passive"))
      (node (ref "C6") (pin "P$1") (pinfunction "P$1_P$1") (pintype "passive"))
      (node (ref "F1") (pin "P$5") (pinfunction "P$2_P$5") (pintype "bidirectional"))
      (node (ref "F1") (pin "P$6") (pinfunction "P$2_P$6") (pintype "bidirectional"))
      (node (ref "F1") (pin "P$7") (pinfunction "P$2_P$7") (pintype "bidirectional"))
      (node (ref "F1") (pin "P$8") (pinfunction "P$2_P$8") (pintype "bidirectional"))
      (node (ref "L1") (pin "P$1") (pinfunction "P$1_P$1") (pintype "passive"))
      (node (ref "L2") (pin "P$1") (pinfunction "P$1_P$1") (pintype "passive"))
      (node (ref "L3") (pin "P$1") (pinfunction "P$1_P$1") (pintype "passive"))
      (node (ref "L4") (pin "P$1") (pinfunction "P$1_P$1") (pintype "passive"))
      (node (ref "U1") (pin "1") (pinfunction "ENA_1") (pintype "bidirectional"))
      (node (ref "U1") (pin "6") (pinfunction "VDD_6") (pintype "bidirectional"))
      (node (ref "U1") (pin "8") (pinfunction "ENB_8") (pintype "bidirectional"))
      (node (ref "U2") (pin "1") (pinfunction "ENA_1") (pintype "bidirectional"))
      (node (ref "U2") (pin "6") (pinfunction "VDD_6") (pintype "bidirectional"))
      (node (ref "U2") (pin "8") (pinfunction "ENB_8") (pintype "bidirectional"))
    )
    (net (code "202") (name "VB2") (class "Default")
      (node (ref "C17") (pin "P$1") (pinfunction "P$1_P$1") (pintype "passive"))
      (node (ref "C18") (pin "P$1") (pinfunction "P$1_P$1") (pintype "passive"))
      (node (ref "C23") (pin "P$1") (pinfunction "P$1_P$1") (pintype "passive"))
      (node (ref "C24") (pin "P$1") (pinfunction "P$1_P$1") (pintype "passive"))
      (node (ref "F2") (pin "P$5") (pinfunction "P$2_P$5") (pintype "bidirectional"))
      (node (ref "F2") (pin "P$6") (pinfunction "P$2_P$6") (pintype "bidirectional"))
      (node (ref "F2") (pin "P$7") (pinfunction "P$2_P$7") (pintype "bidirectional"))
      (node (ref "F2") (pin "P$8") (pinfunction "P$2_P$8") (pintype "bidirectional"))
      (node (ref "L5") (pin "P$1") (pinfunction "P$1_P$1") (pintype "passive"))
      (node (ref "L6") (pin "P$1") (pinfunction "P$1_P$1") (pintype "passive"))
      (node (ref "L7") (pin "P$1") (pinfunction "P$1_P$1") (pintype "passive"))
      (node (ref "L8") (pin "P$1") (pinfunction "P$1_P$1") (pintype "passive"))
      (node (ref "U3") (pin "1") (pinfunction "ENA_1") (pintype "bidirectional"))
      (node (ref "U3") (pin "6") (pinfunction "VDD_6") (pintype "bidirectional"))
      (node (ref "U3") (pin "8") (pinfunction "ENB_8") (pintype "bidirectional"))
      (node (ref "U4") (pin "1") (pinfunction "ENA_1") (pintype "bidirectional"))
      (node (ref "U4") (pin "6") (pinfunction "VDD_6") (pintype "bidirectional"))
      (node (ref "U4") (pin "8") (pinfunction "ENB_8") (pintype "bidirectional"))
    )
    (net (code "203") (name "VIN") (class "Default")
      (node (ref "POWER") (pin "8") (pinfunction "8_8") (pintype "passive"))
    )
    (net (code "204") (name "unconnected-(COMMUNICATION-Pad2)") (class "Default")
      (node (ref "COMMUNICATION") (pin "2") (pinfunction "2_2") (pintype "passive"))
    )
    (net (code "205") (name "unconnected-(POWER-Pad1)") (class "Default")
      (node (ref "POWER") (pin "1") (pinfunction "1_1") (pintype "passive"))
    )
    (net (code "206") (name "unconnected-(PWML-Pad1)") (class "Default")
      (node (ref "PWML") (pin "1") (pinfunction "1_1") (pintype "passive"))
    )
    (net (code "207") (name "unconnected-(PWML-Pad2)") (class "Default")
      (node (ref "PWML") (pin "2") (pinfunction "2_2") (pintype "passive"))
    )
    (net (code "208") (name "unconnected-(PWML-Pad5)") (class "Default")
      (node (ref "PWML") (pin "5") (pinfunction "5_5") (pintype "passive"))
    )
    (net (code "209") (name "unconnected-(RELAY3-Pad87A)") (class "Default")
      (node (ref "RELAY3") (pin "87A") (pinfunction "87A_87A") (pintype "bidirectional"))
    )
    (net (code "210") (name "unconnected-(TP1-PadT)") (class "Default")
      (node (ref "TP1") (pin "T") (pinfunction "T_T") (pintype "bidirectional"))
    )
    (net (code "211") (name "unconnected-(TP2-PadT)") (class "Default")
      (node (ref "TP2") (pin "T") (pinfunction "T_T") (pintype "bidirectional"))
    )
    (net (code "212") (name "unconnected-(TP3-PadT)") (class "Default")
      (node (ref "TP3") (pin "T") (pinfunction "T_T") (pintype "bidirectional"))
    )
    (net (code "213") (name "unconnected-(U14-VREF-Pad5)") (class "Default")
      (node (ref "U14") (pin "5") (pinfunction "VREF_5") (pintype "bidirectional"))
    )
    (net (code "214") (name "unconnected-(U15-CLKOUT{slash}SOF-Pad3)") (class "Default")
      (node (ref "U15") (pin "3") (pinfunction "CLKOUT/SOF_3") (pintype "output"))
    )
    (net (code "215") (name "unconnected-(U15-~{RX0BF}-Pad11)") (class "Default")
      (node (ref "U15") (pin "11") (pinfunction "~{RX0BF}_11") (pintype "output"))
    )
    (net (code "216") (name "unconnected-(U15-~{RX1BF}-Pad10)") (class "Default")
      (node (ref "U15") (pin "10") (pinfunction "~{RX1BF}_10") (pintype "output"))
    )
    (net (code "217") (name "unconnected-(U15-~{TX0RTS}-Pad4)") (class "Default")
      (node (ref "U15") (pin "4") (pinfunction "~{TX0RTS}_4") (pintype "input"))
    )
    (net (code "218") (name "unconnected-(U15-~{TX1RTS}-Pad5)") (class "Default")
      (node (ref "U15") (pin "5") (pinfunction "~{TX1RTS}_5") (pintype "input"))
    )
    (net (code "219") (name "unconnected-(U15-~{TX2RTS}-Pad6)") (class "Default")
      (node (ref "U15") (pin "6") (pinfunction "~{TX2RTS}_6") (pintype "input"))
    )
    (net (code "220") (name "unconnected-(XIO-Pad1)") (class "Default")
      (node (ref "XIO") (pin "1") (pinfunction "1_1") (pintype "passive"))
    )
    (net (code "221") (name "unconnected-(XIO-Pad2)") (class "Default")
      (node (ref "XIO") (pin "2") (pinfunction "2_2") (pintype "passive"))
    )
  )
)
